# P03_SOM_CONNECTOR_CON0.net
KiCad netlist of a schematic drawn in Altium Designer
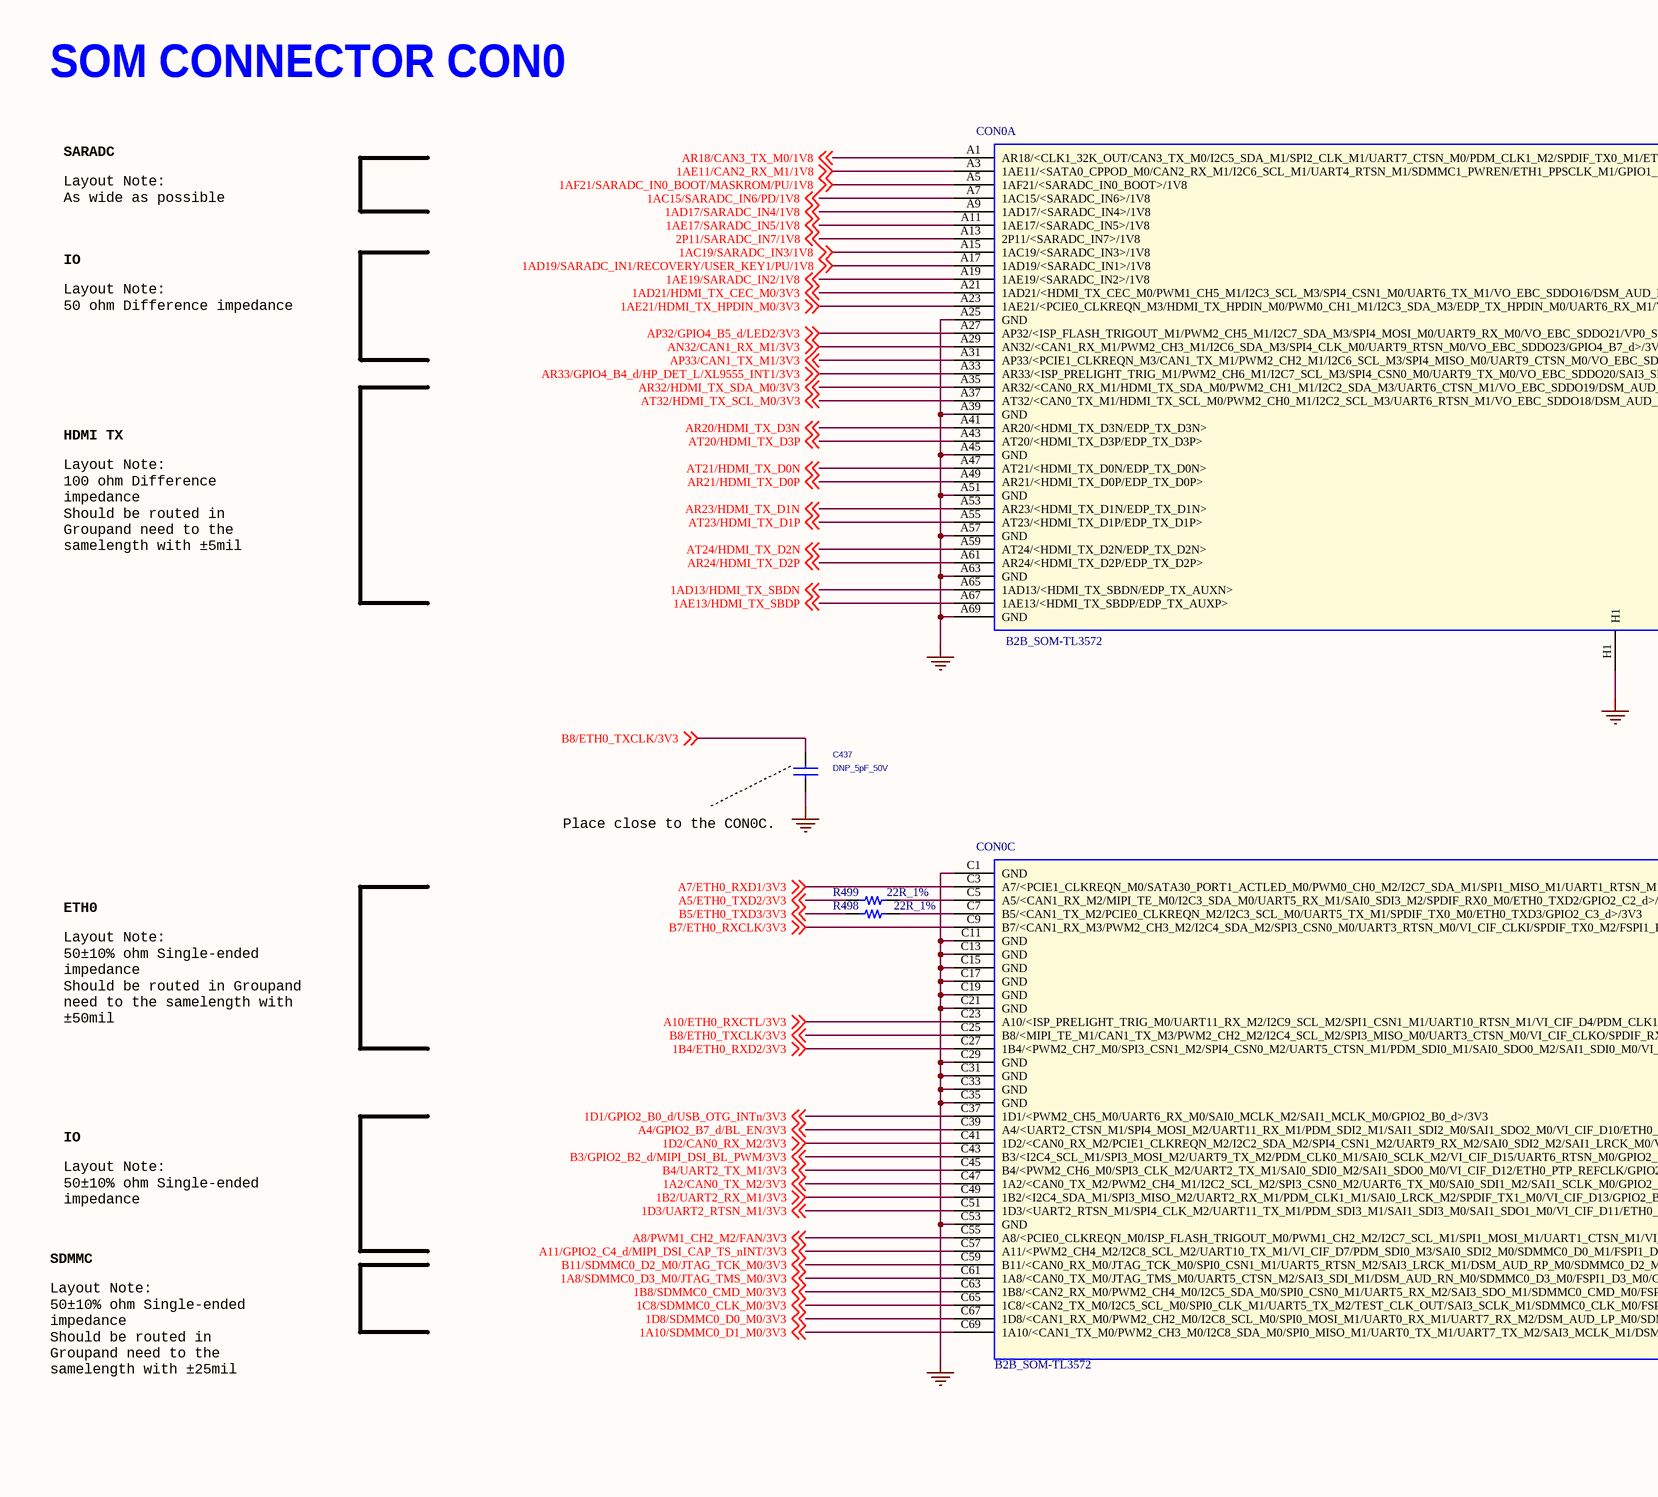
[diagram p0: P03_SOM CONNECTOR CON0.SchDoc, top left]
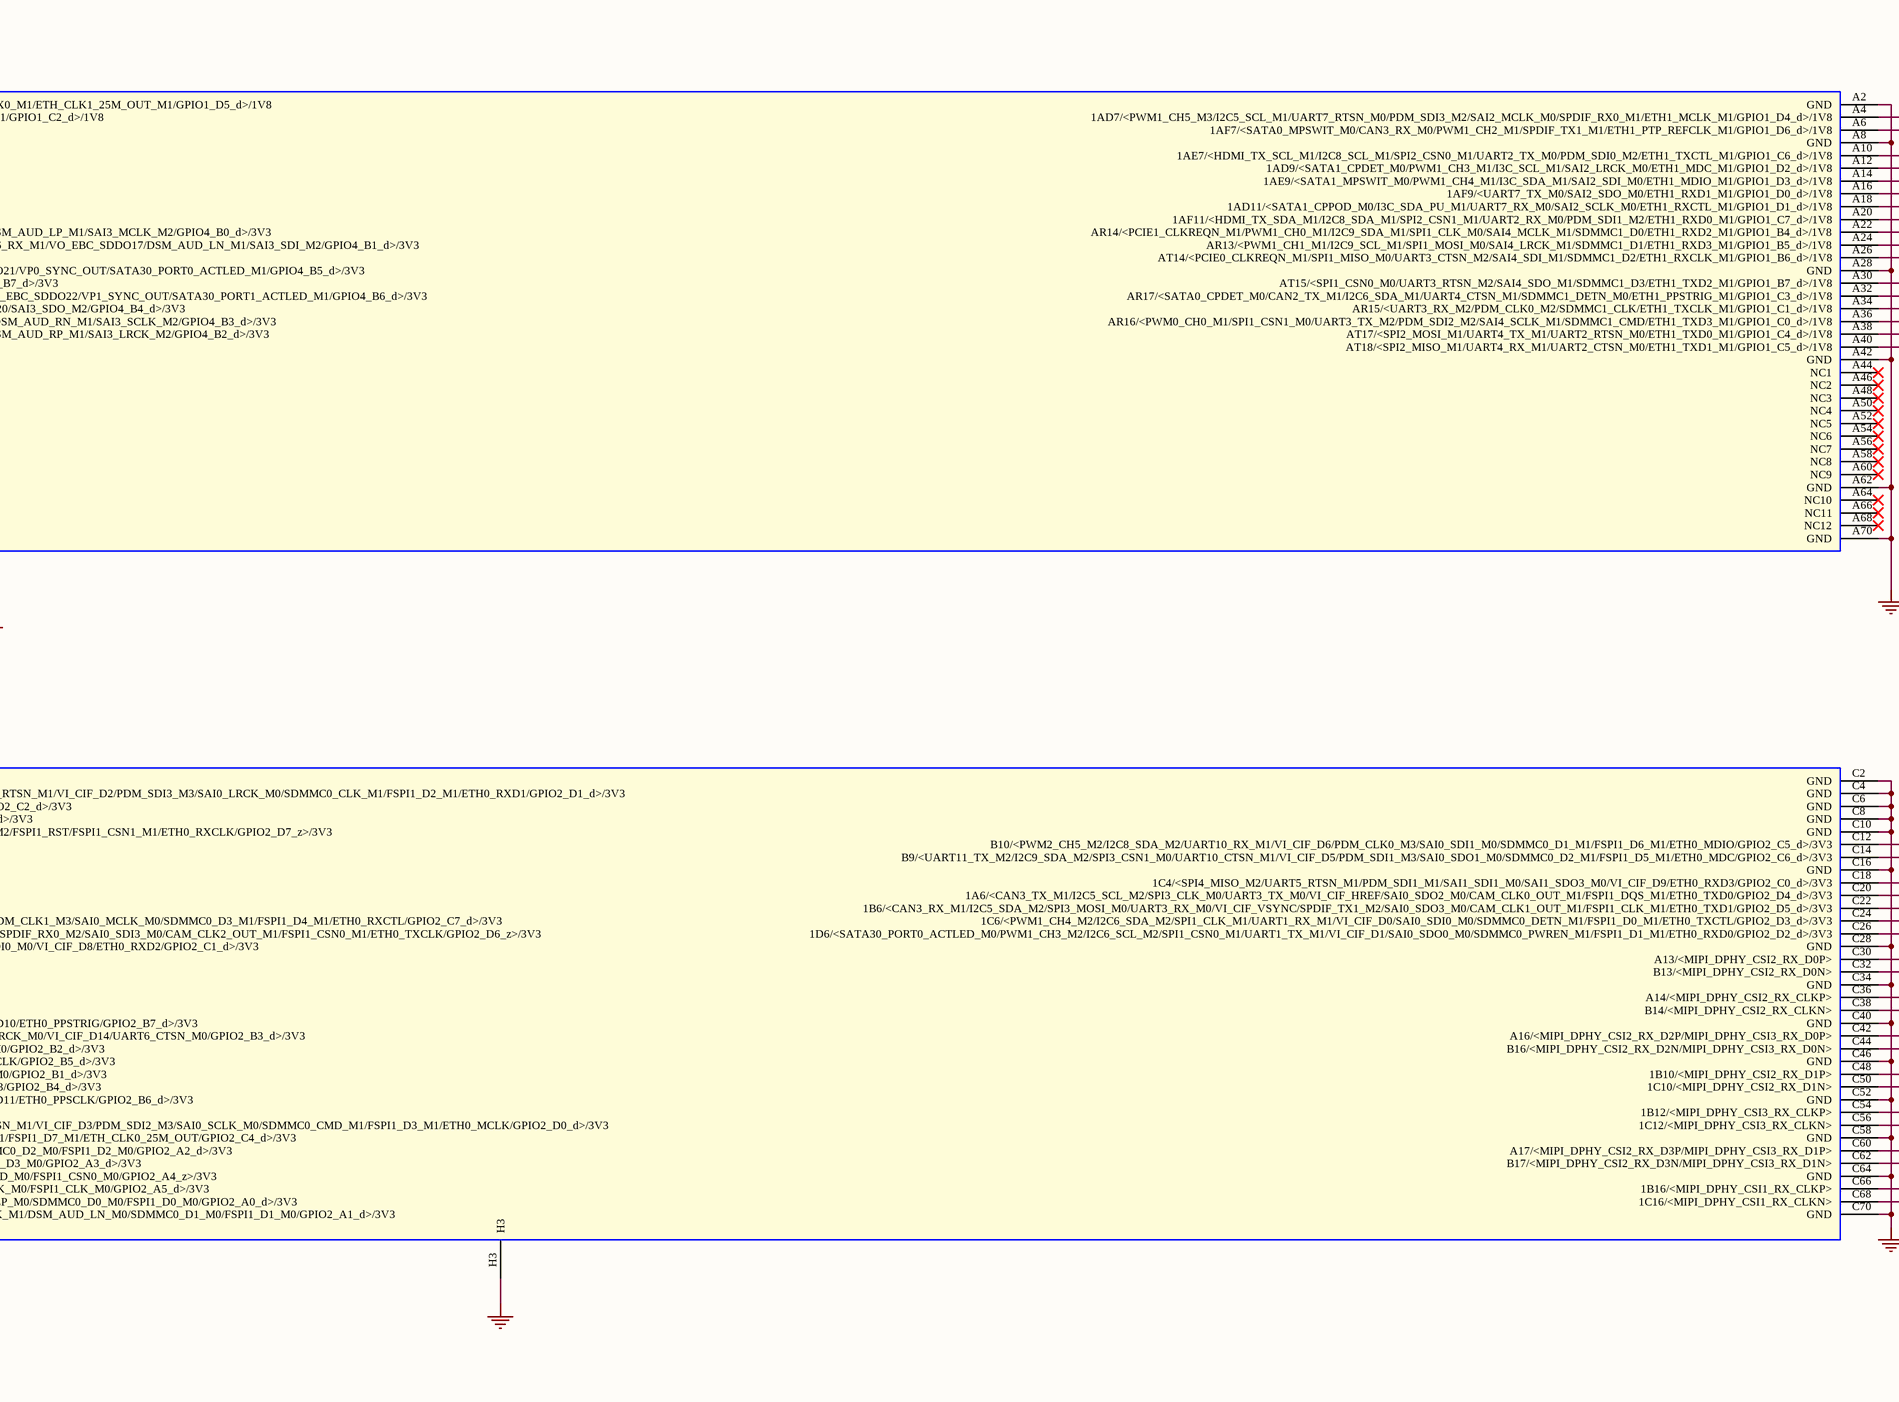
[diagram p1: P03_SOM CONNECTOR CON0.SchDoc, top middle]
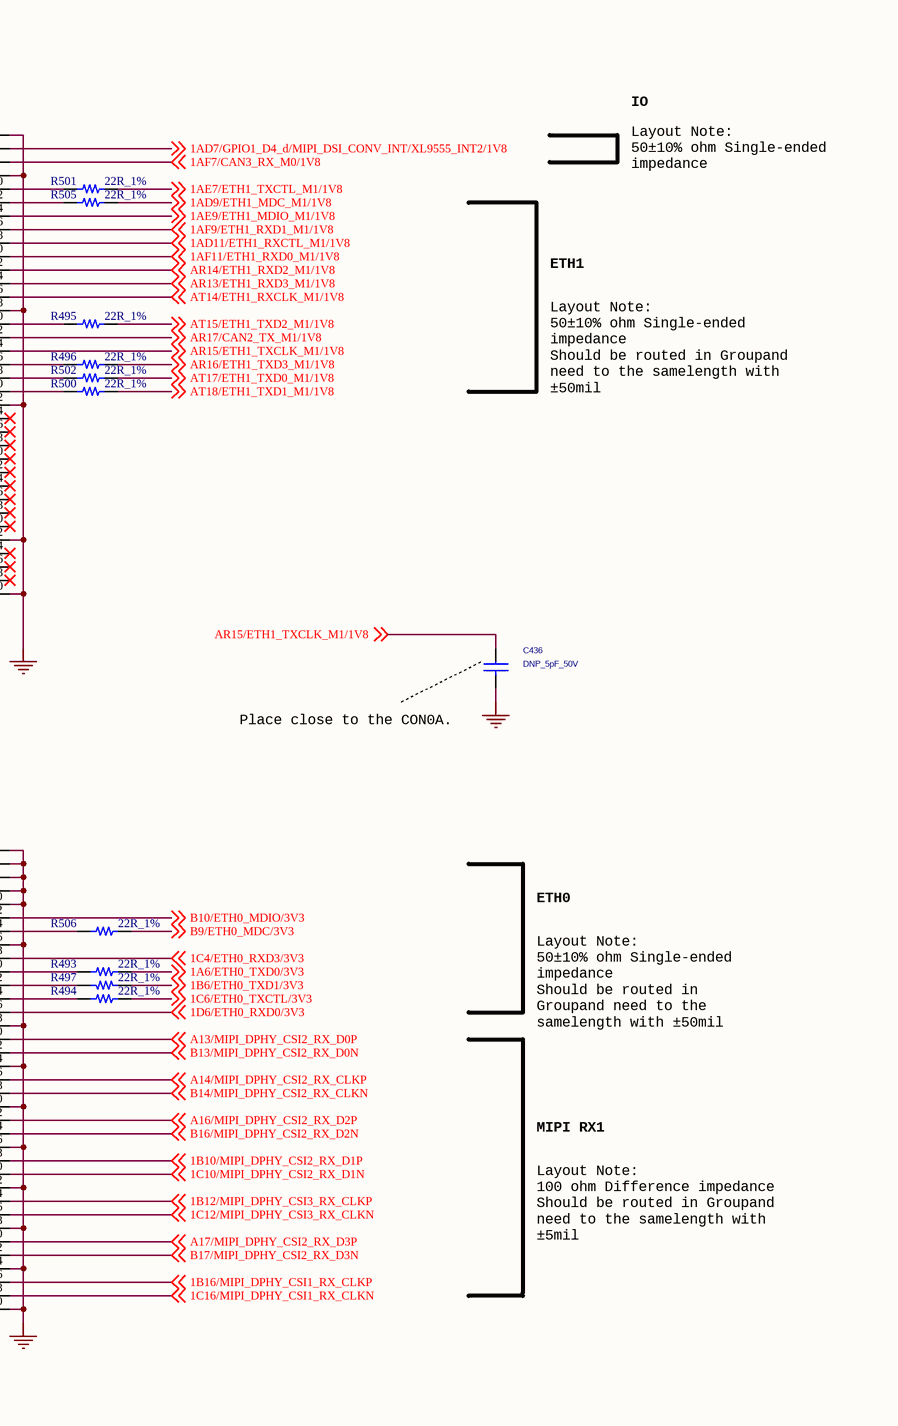
[diagram p2: P03_SOM CONNECTOR CON0.SchDoc, top right]
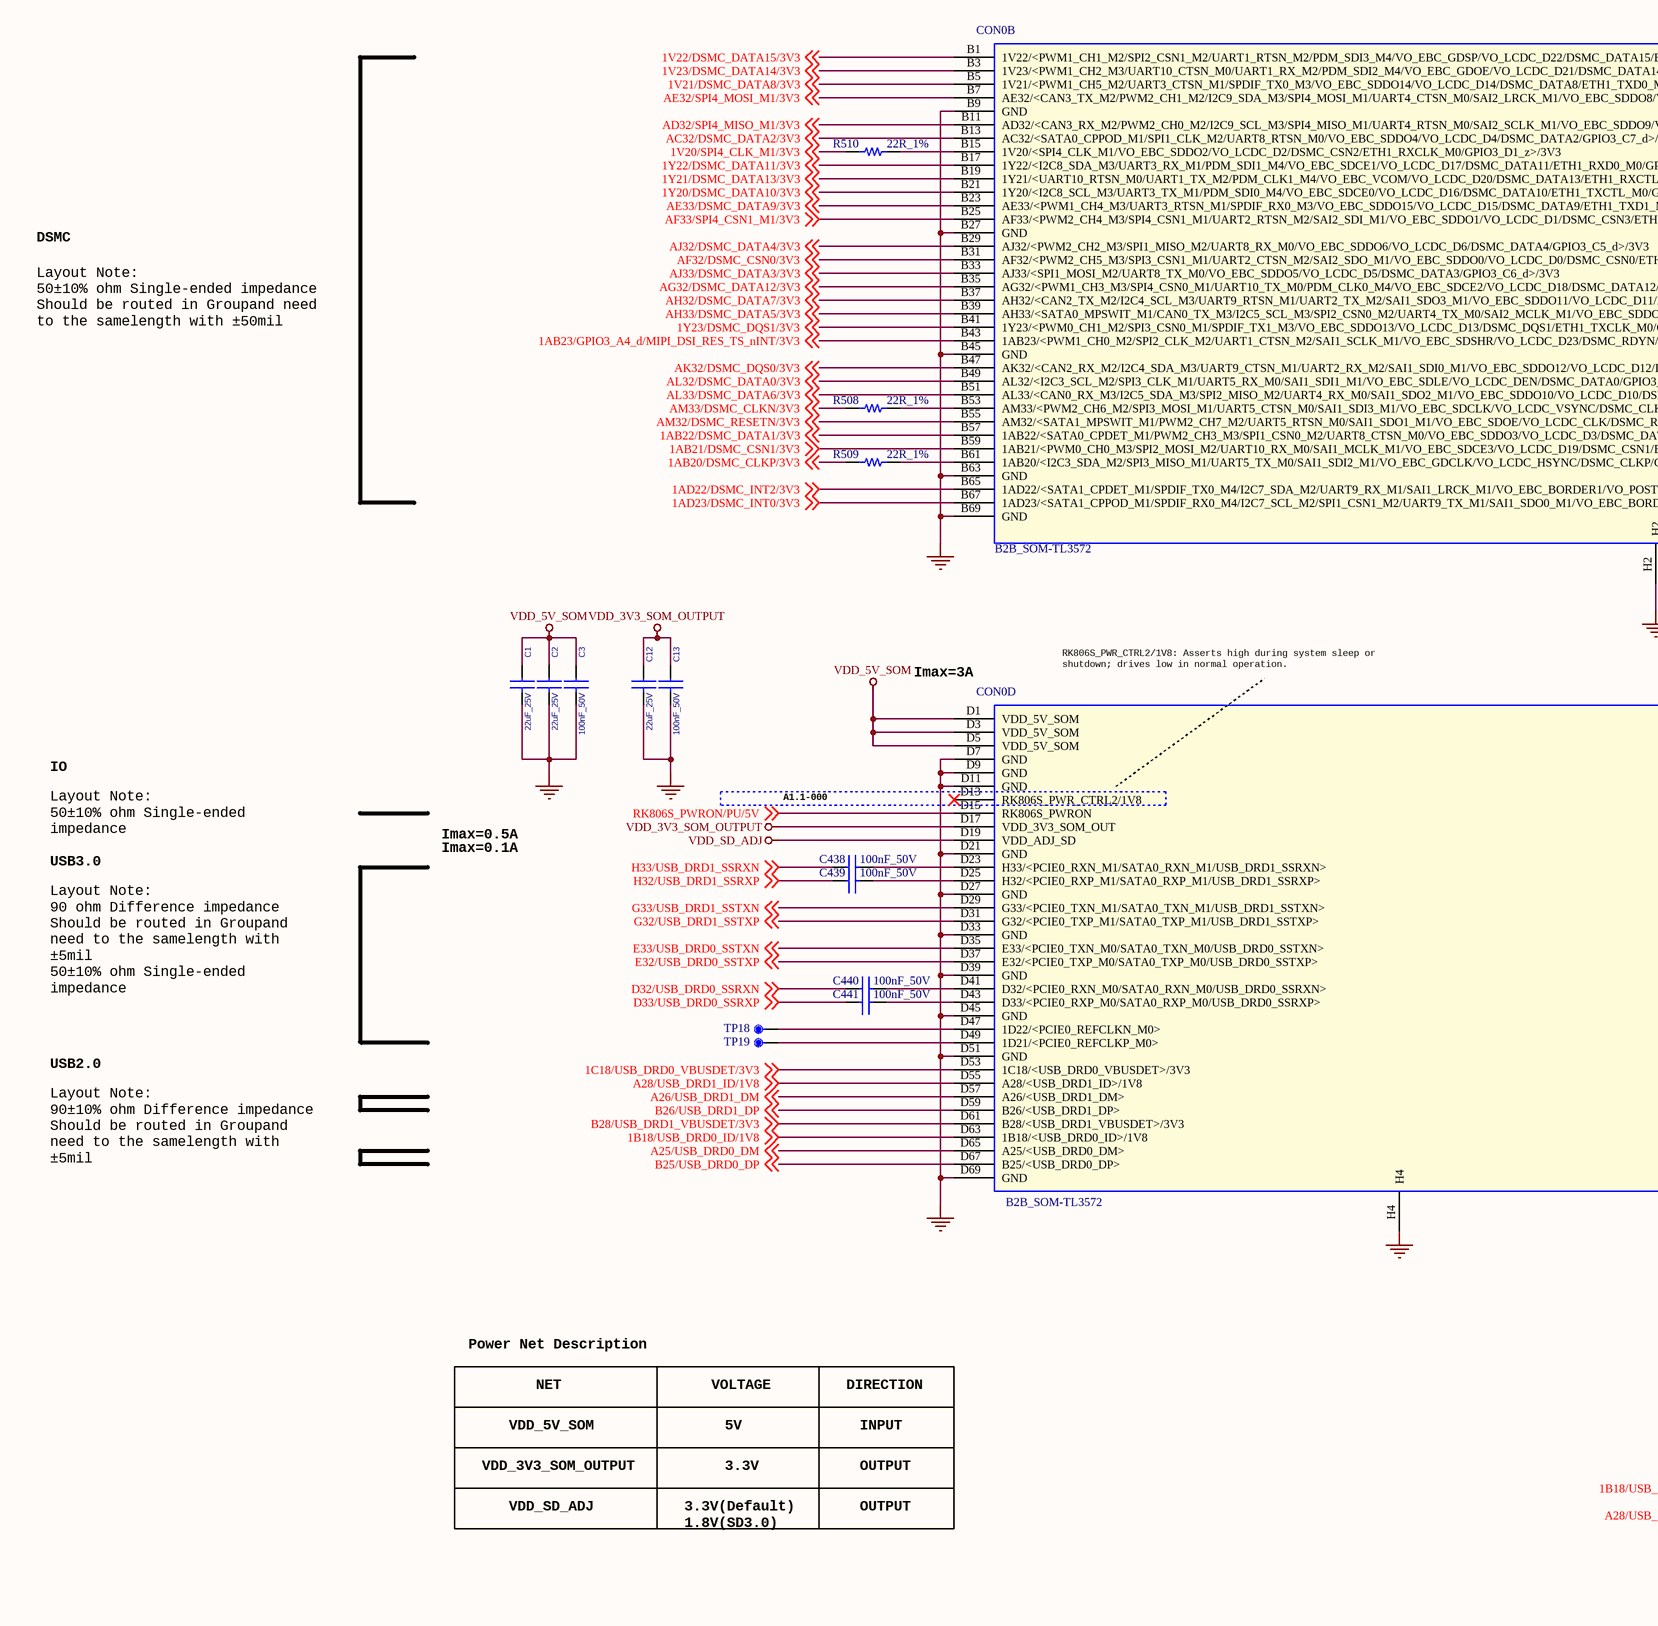
[diagram p3: P03_SOM CONNECTOR CON0.SchDoc, bottom left]
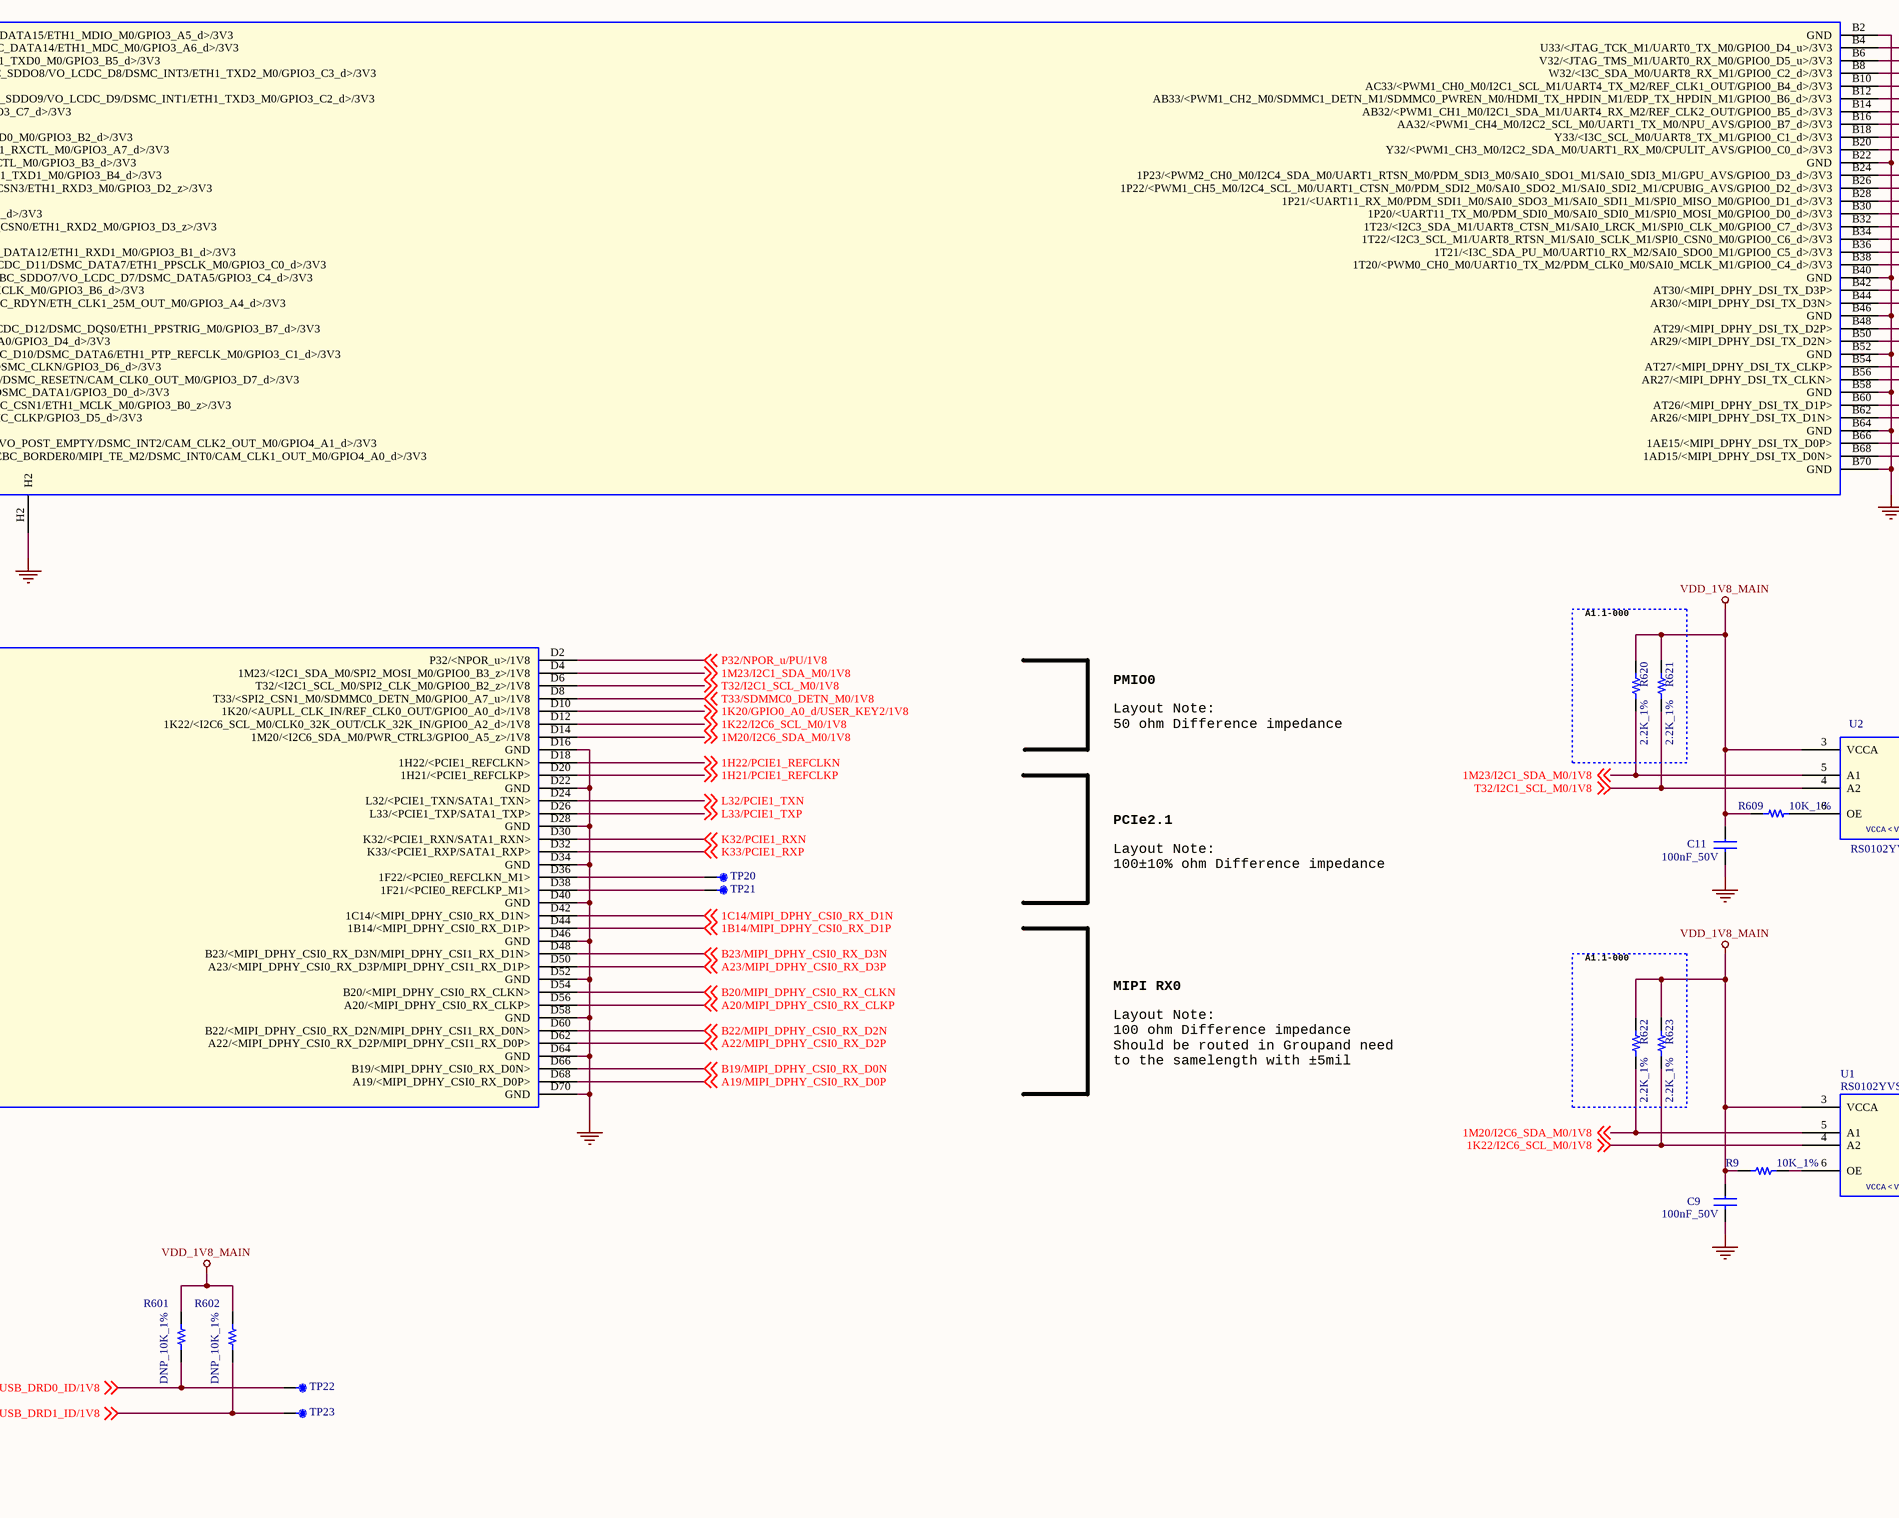
[diagram p4: P03_SOM CONNECTOR CON0.SchDoc, bottom middle]
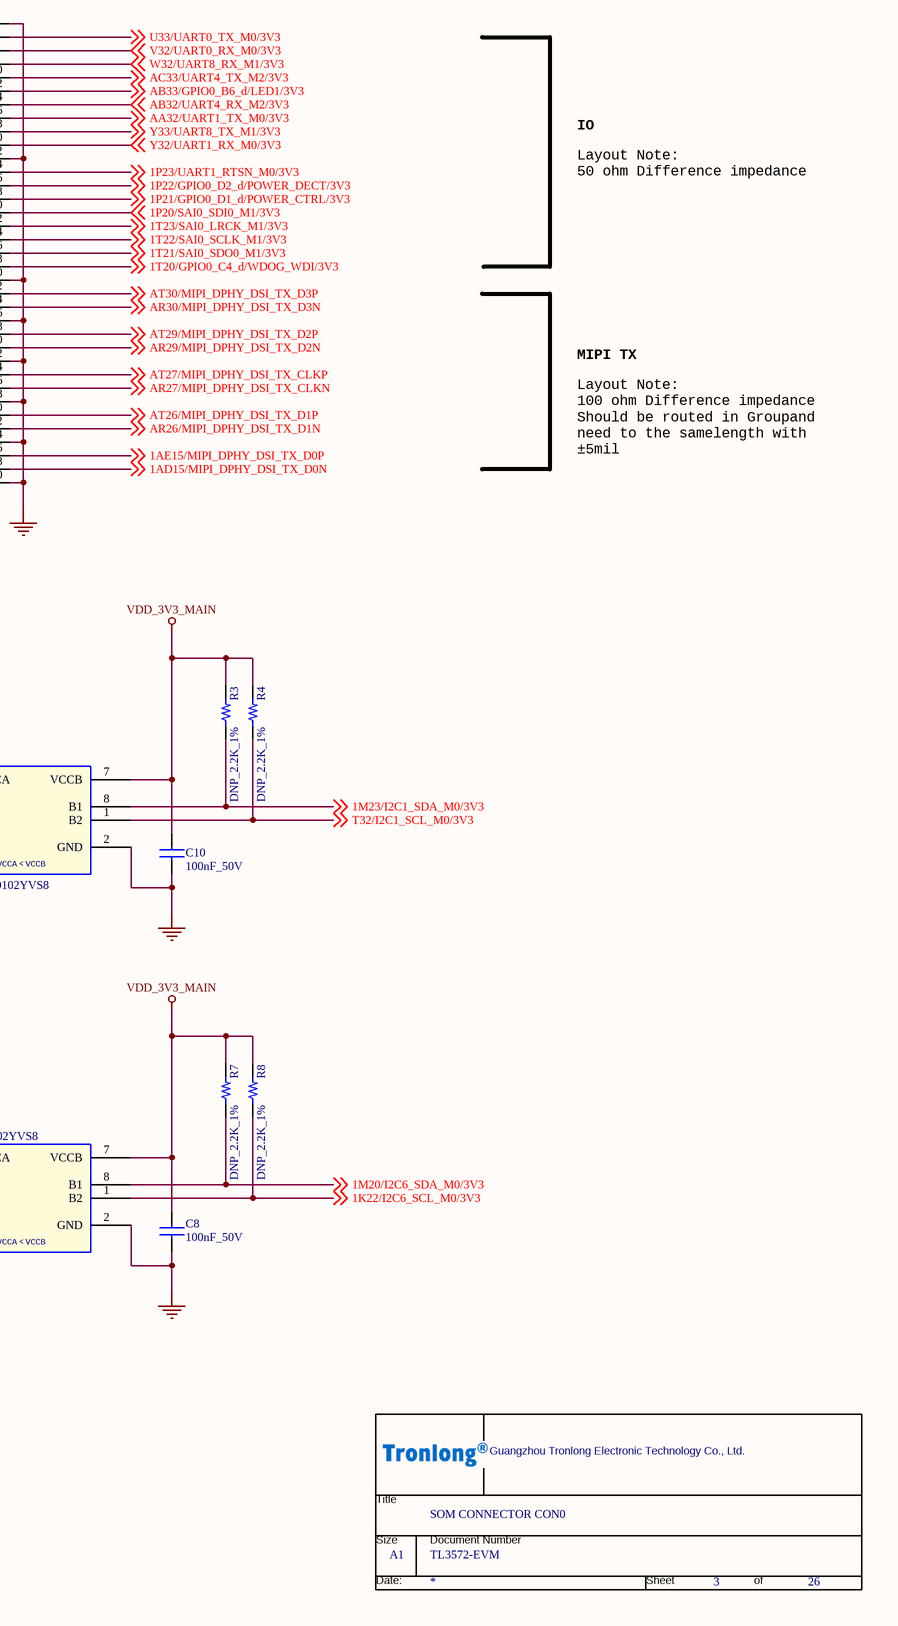
[diagram p5: P03_SOM CONNECTOR CON0.SchDoc, bottom right]

(export (version "E")
  (design (tool "Eeschema 10.0.6"))
  (components
    (comp (ref "C1")
      (value "22uF_25V")
      (footprint "C0805")
      (description "贴片陶瓷电容,22uF,20%,25V,X5R")
      (fields
        (field (name "MANUFACTURER") "广东风华高新科技股份有限公司（FH）")
        (field (name "MANUFACTURER PARTNUMBER") "0805X226M250NT")
      )
      (libsource (lib "*") (part "CAP NP_Dup2"))
    )
    (comp (ref "C2")
      (value "22uF_25V")
      (footprint "C0805")
      (description "贴片陶瓷电容,22uF,20%,25V,X5R")
      (fields
        (field (name "MANUFACTURER") "广东风华高新科技股份有限公司（FH）")
        (field (name "MANUFACTURER PARTNUMBER") "0805X226M250NT")
      )
      (libsource (lib "*") (part "CAP NP_Dup2"))
    )
    (comp (ref "C3")
      (value "100nF_50V")
      (footprint "C0402")
      (description "贴片陶瓷电容,100nF,10%,50V,X7R")
      (fields
        (field (name "MANUFACTURER PARTNUMBER") "0402B104K500NT")
        (field (name "MANUFACTURER") "广东风华高新科技股份有限公司（FH）")
      )
      (libsource (lib "*") (part "CAP NP_Dup2"))
    )
    (comp (ref "C8")
      (value "100nF_50V")
      (footprint "C0402")
      (description "贴片陶瓷电容,100nF,10%,50V,X7R")
      (fields
        (field (name "MANUFACTURER PARTNUMBER") "0402B104K500NT")
        (field (name "MANUFACTURER") "广东风华高新科技股份有限公司（FH）")
      )
      (libsource (lib "*") (part "CAP NP_Dup3"))
    )
    (comp (ref "C9")
      (value "100nF_50V")
      (footprint "C0402")
      (description "贴片陶瓷电容,100nF,10%,50V,X7R")
      (fields
        (field (name "MANUFACTURER PARTNUMBER") "0402B104K500NT")
        (field (name "MANUFACTURER") "广东风华高新科技股份有限公司（FH）")
      )
      (libsource (lib "*") (part "CAP NP_Dup3"))
    )
    (comp (ref "C10")
      (value "100nF_50V")
      (footprint "C0402")
      (description "贴片陶瓷电容,100nF,10%,50V,X7R")
      (fields
        (field (name "MANUFACTURER PARTNUMBER") "0402B104K500NT")
        (field (name "MANUFACTURER") "广东风华高新科技股份有限公司（FH）")
      )
      (libsource (lib "*") (part "CAP NP_Dup3"))
    )
    (comp (ref "C11")
      (value "100nF_50V")
      (footprint "C0402")
      (description "贴片陶瓷电容,100nF,10%,50V,X7R")
      (fields
        (field (name "MANUFACTURER") "广东风华高新科技股份有限公司（FH）")
        (field (name "MANUFACTURER PARTNUMBER") "0402B104K500NT")
      )
      (libsource (lib "*") (part "CAP NP_Dup3"))
    )
    (comp (ref "C12")
      (value "22uF_25V")
      (footprint "C0805")
      (description "贴片陶瓷电容,22uF,20%,25V,X5R")
      (fields
        (field (name "MANUFACTURER PARTNUMBER") "0805X226M250NT")
        (field (name "MANUFACTURER") "广东风华高新科技股份有限公司（FH）")
      )
      (libsource (lib "*") (part "CAP NP_Dup2"))
    )
    (comp (ref "C13")
      (value "100nF_50V")
      (footprint "C0402")
      (description "贴片陶瓷电容,100nF,10%,50V,X7R")
      (fields
        (field (name "MANUFACTURER PARTNUMBER") "0402B104K500NT")
        (field (name "MANUFACTURER") "广东风华高新科技股份有限公司（FH）")
      )
      (libsource (lib "*") (part "CAP NP_Dup2"))
    )
    (comp (ref "C436")
      (value "DNP_5pF_50V")
      (footprint "C0402")
      (description "贴片陶瓷电容,22pF,5%,50V,COG")
      (fields
        (field (name "MANUFACTURER") "广东风华高新科技股份有限公司（FH）")
        (field (name "MANUFACTURER PARTNUMBER") "0402CG220J500NT")
      )
      (libsource (lib "*") (part "CAP NP_Dup2"))
    )
    (comp (ref "C437")
      (value "DNP_5pF_50V")
      (footprint "C0402")
      (description "贴片陶瓷电容,22pF,5%,50V,COG")
      (fields
        (field (name "MANUFACTURER") "广东风华高新科技股份有限公司（FH）")
        (field (name "MANUFACTURER PARTNUMBER") "0402CG220J500NT")
      )
      (libsource (lib "*") (part "CAP NP_Dup2"))
    )
    (comp (ref "C438")
      (value "100nF_50V")
      (footprint "C0402")
      (description "贴片陶瓷电容,100nF,10%,50V,X7R")
      (fields
        (field (name "MANUFACTURER PARTNUMBER") "0402B104K500NT")
        (field (name "MANUFACTURER") "广东风华高新科技股份有限公司（FH）")
      )
      (libsource (lib "*") (part "CAP NP_Dup2"))
    )
    (comp (ref "C439")
      (value "100nF_50V")
      (footprint "C0402")
      (description "贴片陶瓷电容,100nF,10%,50V,X7R")
      (fields
        (field (name "MANUFACTURER") "广东风华高新科技股份有限公司（FH）")
        (field (name "MANUFACTURER PARTNUMBER") "0402B104K500NT")
      )
      (libsource (lib "*") (part "CAP NP_Dup2"))
    )
    (comp (ref "C440")
      (value "100nF_50V")
      (footprint "C0402")
      (description "贴片陶瓷电容,100nF,10%,50V,X7R")
      (fields
        (field (name "MANUFACTURER PARTNUMBER") "0402B104K500NT")
        (field (name "MANUFACTURER") "广东风华高新科技股份有限公司（FH）")
      )
      (libsource (lib "*") (part "CAP NP_Dup2"))
    )
    (comp (ref "C441")
      (value "100nF_50V")
      (footprint "C0402")
      (description "贴片陶瓷电容,100nF,10%,50V,X7R")
      (fields
        (field (name "MANUFACTURER PARTNUMBER") "0402B104K500NT")
        (field (name "MANUFACTURER") "广东风华高新科技股份有限公司（FH）")
      )
      (libsource (lib "*") (part "CAP NP_Dup2"))
    )
    (comp (ref "CON0")
      (value "B2B_SOM-TL3572")
      (footprint "B2B_SOM-TL3572")
      (libsource (lib "TL3572-EVM-A1.1-000-r-202609030936") (part "B2B_SOM-TL3572"))
    )
    (comp (ref "R3")
      (value "DNP_2.2K_1%")
      (footprint "R0402")
      (description "贴片电阻,2.2K,±1%,1/16W")
      (fields
        (field (name "MANUFACTURER PARTNUMBER") "RC-02K2201FT")
        (field (name "MANUFACTURER") "广东风华高新科技股份有限公司（FH）")
      )
      (libsource (lib "*") (part "Resistor_Dup4"))
    )
    (comp (ref "R4")
      (value "DNP_2.2K_1%")
      (footprint "R0402")
      (description "贴片电阻,2.2K,±1%,1/16W")
      (fields
        (field (name "MANUFACTURER PARTNUMBER") "RC-02K2201FT")
        (field (name "MANUFACTURER") "广东风华高新科技股份有限公司（FH）")
      )
      (libsource (lib "*") (part "Resistor_Dup4"))
    )
    (comp (ref "R7")
      (value "DNP_2.2K_1%")
      (footprint "R0402")
      (description "贴片电阻,2.2K,±1%,1/16W")
      (fields
        (field (name "MANUFACTURER") "广东风华高新科技股份有限公司（FH）")
        (field (name "MANUFACTURER PARTNUMBER") "RC-02K2201FT")
      )
      (libsource (lib "*") (part "Resistor_Dup4"))
    )
    (comp (ref "R8")
      (value "DNP_2.2K_1%")
      (footprint "R0402")
      (description "贴片电阻,2.2K,±1%,1/16W")
      (fields
        (field (name "MANUFACTURER PARTNUMBER") "RC-02K2201FT")
        (field (name "MANUFACTURER") "广东风华高新科技股份有限公司（FH）")
      )
      (libsource (lib "*") (part "Resistor_Dup4"))
    )
    (comp (ref "R9")
      (value "10K_1%")
      (footprint "R0402")
      (description "贴片电阻,10K,±1%,1/16W")
      (fields
        (field (name "MANUFACTURER") "广东风华高新科技股份有限公司（FH）")
        (field (name "MANUFACTURER PARTNUMBER") "RC-02K1002FT")
      )
      (libsource (lib "*") (part "Resistor_Dup4"))
    )
    (comp (ref "R493")
      (value "22R_1%")
      (footprint "R0402")
      (description "贴片电阻,22R,±1%,1/16W")
      (fields
        (field (name "MANUFACTURER") "广东风华高新科技股份有限公司（FH）")
        (field (name "MANUFACTURER PARTNUMBER") "RC-02K22R0FT")
      )
      (libsource (lib "*") (part "Resistor_Dup3"))
    )
    (comp (ref "R494")
      (value "22R_1%")
      (footprint "R0402")
      (description "贴片电阻,22R,±1%,1/16W")
      (fields
        (field (name "MANUFACTURER PARTNUMBER") "RC-02K22R0FT")
        (field (name "MANUFACTURER") "广东风华高新科技股份有限公司（FH）")
      )
      (libsource (lib "*") (part "Resistor_Dup3"))
    )
    (comp (ref "R495")
      (value "22R_1%")
      (footprint "R0402")
      (description "贴片电阻,22R,±1%,1/16W")
      (fields
        (field (name "MANUFACTURER PARTNUMBER") "RC-02K22R0FT")
        (field (name "MANUFACTURER") "广东风华高新科技股份有限公司（FH）")
      )
      (libsource (lib "*") (part "Resistor_Dup3"))
    )
    (comp (ref "R496")
      (value "22R_1%")
      (footprint "R0402")
      (description "贴片电阻,22R,±1%,1/16W")
      (fields
        (field (name "MANUFACTURER PARTNUMBER") "RC-02K22R0FT")
        (field (name "MANUFACTURER") "广东风华高新科技股份有限公司（FH）")
      )
      (libsource (lib "*") (part "Resistor_Dup3"))
    )
    (comp (ref "R497")
      (value "22R_1%")
      (footprint "R0402")
      (description "贴片电阻,22R,±1%,1/16W")
      (fields
        (field (name "MANUFACTURER PARTNUMBER") "RC-02K22R0FT")
        (field (name "MANUFACTURER") "广东风华高新科技股份有限公司（FH）")
      )
      (libsource (lib "*") (part "Resistor_Dup3"))
    )
    (comp (ref "R498")
      (value "22R_1%")
      (footprint "R0402")
      (description "贴片电阻,22R,±1%,1/16W")
      (fields
        (field (name "MANUFACTURER PARTNUMBER") "RC-02K22R0FT")
        (field (name "MANUFACTURER") "广东风华高新科技股份有限公司（FH）")
      )
      (libsource (lib "*") (part "Resistor_Dup3"))
    )
    (comp (ref "R499")
      (value "22R_1%")
      (footprint "R0402")
      (description "贴片电阻,22R,±1%,1/16W")
      (fields
        (field (name "MANUFACTURER") "广东风华高新科技股份有限公司（FH）")
        (field (name "MANUFACTURER PARTNUMBER") "RC-02K22R0FT")
      )
      (libsource (lib "*") (part "Resistor_Dup3"))
    )
    (comp (ref "R500")
      (value "22R_1%")
      (footprint "R0402")
      (description "贴片电阻,22R,±1%,1/16W")
      (fields
        (field (name "MANUFACTURER") "广东风华高新科技股份有限公司（FH）")
        (field (name "MANUFACTURER PARTNUMBER") "RC-02K22R0FT")
      )
      (libsource (lib "*") (part "Resistor_Dup3"))
    )
    (comp (ref "R501")
      (value "22R_1%")
      (footprint "R0402")
      (description "贴片电阻,22R,±1%,1/16W")
      (fields
        (field (name "MANUFACTURER") "广东风华高新科技股份有限公司（FH）")
        (field (name "MANUFACTURER PARTNUMBER") "RC-02K22R0FT")
      )
      (libsource (lib "*") (part "Resistor_Dup3"))
    )
    (comp (ref "R502")
      (value "22R_1%")
      (footprint "R0402")
      (description "贴片电阻,22R,±1%,1/16W")
      (fields
        (field (name "MANUFACTURER PARTNUMBER") "RC-02K22R0FT")
        (field (name "MANUFACTURER") "广东风华高新科技股份有限公司（FH）")
      )
      (libsource (lib "*") (part "Resistor_Dup3"))
    )
    (comp (ref "R505")
      (value "22R_1%")
      (footprint "R0402")
      (description "贴片电阻,22R,±1%,1/16W")
      (fields
        (field (name "MANUFACTURER") "广东风华高新科技股份有限公司（FH）")
        (field (name "MANUFACTURER PARTNUMBER") "RC-02K22R0FT")
      )
      (libsource (lib "*") (part "Resistor_Dup3"))
    )
    (comp (ref "R506")
      (value "22R_1%")
      (footprint "R0402")
      (description "贴片电阻,22R,±1%,1/16W")
      (fields
        (field (name "MANUFACTURER PARTNUMBER") "RC-02K22R0FT")
        (field (name "MANUFACTURER") "广东风华高新科技股份有限公司（FH）")
      )
      (libsource (lib "*") (part "Resistor_Dup3"))
    )
    (comp (ref "R508")
      (value "22R_1%")
      (footprint "R0402")
      (description "贴片电阻,22R,±1%,1/16W")
      (fields
        (field (name "MANUFACTURER") "广东风华高新科技股份有限公司（FH）")
        (field (name "MANUFACTURER PARTNUMBER") "RC-02K22R0FT")
      )
      (libsource (lib "*") (part "Resistor_Dup3"))
    )
    (comp (ref "R509")
      (value "22R_1%")
      (footprint "R0402")
      (description "贴片电阻,22R,±1%,1/16W")
      (fields
        (field (name "MANUFACTURER") "广东风华高新科技股份有限公司（FH）")
        (field (name "MANUFACTURER PARTNUMBER") "RC-02K22R0FT")
      )
      (libsource (lib "*") (part "Resistor_Dup3"))
    )
    (comp (ref "R510")
      (value "22R_1%")
      (footprint "R0402")
      (description "贴片电阻,22R,±1%,1/16W")
      (fields
        (field (name "MANUFACTURER") "广东风华高新科技股份有限公司（FH）")
        (field (name "MANUFACTURER PARTNUMBER") "RC-02K22R0FT")
      )
      (libsource (lib "*") (part "Resistor_Dup3"))
    )
    (comp (ref "R601")
      (value "DNP_10K_1%")
      (footprint "R0402")
      (description "贴片电阻,10K,±1%,1/16W")
      (fields
        (field (name "MANUFACTURER PARTNUMBER") "RC-02K1002FT")
        (field (name "MANUFACTURER") "广东风华高新科技股份有限公司（FH）")
      )
      (libsource (lib "*") (part "Resistor_Dup4"))
    )
    (comp (ref "R602")
      (value "DNP_10K_1%")
      (footprint "R0402")
      (description "贴片电阻,10K,±1%,1/16W")
      (fields
        (field (name "MANUFACTURER") "广东风华高新科技股份有限公司（FH）")
        (field (name "MANUFACTURER PARTNUMBER") "RC-02K1002FT")
      )
      (libsource (lib "*") (part "Resistor_Dup4"))
    )
    (comp (ref "R609")
      (value "10K_1%")
      (footprint "R0402")
      (description "贴片电阻,10K,±1%,1/16W")
      (fields
        (field (name "MANUFACTURER") "广东风华高新科技股份有限公司（FH）")
        (field (name "MANUFACTURER PARTNUMBER") "RC-02K1002FT")
      )
      (libsource (lib "*") (part "Resistor_Dup4"))
    )
    (comp (ref "R620")
      (value "2.2K_1%")
      (footprint "R0402")
      (description "贴片电阻,2.2K,±1%,1/16W")
      (fields
        (field (name "MANUFACTURER") "广东风华高新科技股份有限公司（FH）")
        (field (name "MANUFACTURER PARTNUMBER") "RC-02K2201FT")
      )
      (libsource (lib "*") (part "Resistor_Dup4"))
    )
    (comp (ref "R621")
      (value "2.2K_1%")
      (footprint "R0402")
      (description "贴片电阻,2.2K,±1%,1/16W")
      (fields
        (field (name "MANUFACTURER") "广东风华高新科技股份有限公司（FH）")
        (field (name "MANUFACTURER PARTNUMBER") "RC-02K2201FT")
      )
      (libsource (lib "*") (part "Resistor_Dup4"))
    )
    (comp (ref "R622")
      (value "2.2K_1%")
      (footprint "R0402")
      (description "贴片电阻,2.2K,±1%,1/16W")
      (fields
        (field (name "MANUFACTURER PARTNUMBER") "RC-02K2201FT")
        (field (name "MANUFACTURER") "广东风华高新科技股份有限公司（FH）")
      )
      (libsource (lib "*") (part "Resistor_Dup4"))
    )
    (comp (ref "R623")
      (value "2.2K_1%")
      (footprint "R0402")
      (description "贴片电阻,2.2K,±1%,1/16W")
      (fields
        (field (name "MANUFACTURER PARTNUMBER") "RC-02K2201FT")
        (field (name "MANUFACTURER") "广东风华高新科技股份有限公司（FH）")
      )
      (libsource (lib "*") (part "Resistor_Dup4"))
    )
    (comp (ref "TP18")
      (value "SMT TP")
      (footprint "TP30")
      (description "/")
      (libsource (lib "*") (part "TP-S40"))
    )
    (comp (ref "TP19")
      (value "SMT TP")
      (footprint "TP30")
      (description "/")
      (libsource (lib "*") (part "TP-S40"))
    )
    (comp (ref "TP20")
      (value "SMT TP")
      (footprint "TP30")
      (description "/")
      (libsource (lib "*") (part "TP-S40"))
    )
    (comp (ref "TP21")
      (value "SMT TP")
      (footprint "TP30")
      (description "/")
      (libsource (lib "*") (part "TP-S40"))
    )
    (comp (ref "TP22")
      (value "SMT TP")
      (footprint "TP30")
      (description "/")
      (libsource (lib "*") (part "TP-S40"))
    )
    (comp (ref "TP23")
      (value "SMT TP")
      (footprint "TP30")
      (description "/")
      (libsource (lib "*") (part "TP-S40"))
    )
    (comp (ref "U1")
      (value "RS0102YVS8")
      (footprint "SOP8-20-91")
      (description "2位双向电平转换器")
      (fields (field (name "MANUFACTURER") "江苏润石科技有限公司（RUNIC）"))
      (libsource (lib "*") (part "TXS0102DCUR_0"))
    )
    (comp (ref "U2")
      (value "RS0102YVS8")
      (footprint "SOP8-20-91")
      (description "2位双向电平转换器")
      (fields (field (name "MANUFACTURER") "江苏润石科技有限公司（RUNIC）"))
      (libsource (lib "*") (part "TXS0102DCUR_0"))
    )
  )
  (nets
    (net (code "1") (name "1A2{slash}CAN0_TX_M2{slash}3V3") (class "Default")
      (node (ref "CON0") (pin "C47") (pinfunction "1A2/<CAN0_TX_M2/PWM2_CH4_M1/I2C2_SCL_M2/SPI3_CSN0_M2/UART6_TX_M0/SAI0_SDI1_M2/SAI1_SCLK_M0/GPIO2_B1_d>/3V3_C47") (pintype "passive"))
    )
    (net (code "2") (name "1A6{slash}ETH0_TXD0{slash}3V3") (class "Default")
      (node (ref "R493") (pin "2") (pinfunction "2_2") (pintype "passive"))
    )
    (net (code "3") (name "1A8{slash}SDMMC0_D3_M0{slash}JTAG_TMS_M0{slash}3V3") (class "Default")
      (node (ref "CON0") (pin "C61") (pinfunction "1A8/<CAN0_TX_M0/JTAG_TMS_M0/UART5_CTSN_M2/SAI3_SDI_M1/DSM_AUD_RN_M0/SDMMC0_D3_M0/FSPI1_D3_M0/GPIO2_A3_d>/3V3_C61") (pintype "passive"))
    )
    (net (code "4") (name "1A10{slash}SDMMC0_D1_M0{slash}3V3") (class "Default")
      (node (ref "CON0") (pin "C69") (pinfunction "1A10/<CAN1_TX_M0/PWM2_CH3_M0/I2C8_SDA_M0/SPI0_MISO_M1/UART0_TX_M1/UART7_TX_M2/SAI3_MCLK_M1/DSM_AUD_LN_M0/SDMMC0_D1_M0/FSPI1_D1_M0/GPIO2_A1_d>/3V3_C69") (pintype "passive"))
    )
    (net (code "5") (name "1AB20{slash}DSMC_CLKP{slash}3V3") (class "Default")
      (node (ref "R509") (pin "1") (pinfunction "1_1") (pintype "passive"))
    )
    (net (code "6") (name "1AB21{slash}DSMC_CSN1{slash}3V3") (class "Default")
      (node (ref "CON0") (pin "B59") (pinfunction "1AB21/<PWM0_CH0_M3/SPI2_MOSI_M2/UART10_RX_M0/SAI1_MCLK_M1/VO_EBC_SDCE3/VO_LCDC_D19/DSMC_CSN1/ETH1_MCLK_M0/GPIO3_B0_z>/3V3_B59") (pintype "passive"))
    )
    (net (code "7") (name "1AB22{slash}DSMC_DATA1{slash}3V3") (class "Default")
      (node (ref "CON0") (pin "B57") (pinfunction "1AB22/<SATA0_CPDET_M1/PWM2_CH3_M3/SPI1_CSN0_M2/UART8_CTSN_M0/VO_EBC_SDDO3/VO_LCDC_D3/DSMC_DATA1/GPIO3_D0_d>/3V3_B57") (pintype "passive"))
    )
    (net (code "8") (name "1AB23{slash}GPIO3_A4_d{slash}MIPI_DSI_RES_TS_nINT{slash}3V3") (class "Default")
      (node (ref "CON0") (pin "B43") (pinfunction "1AB23/<PWM1_CH0_M2/SPI2_CLK_M2/UART1_CTSN_M2/SAI1_SCLK_M1/VO_EBC_SDSHR/VO_LCDC_D23/DSMC_RDYN/ETH_CLK1_25M_OUT_M0/GPIO3_A4_d>/3V3_B43") (pintype "passive"))
    )
    (net (code "9") (name "1AC15{slash}SARADC_IN6{slash}PD{slash}1V8") (class "Default")
      (node (ref "CON0") (pin "A7") (pinfunction "1AC15/<SARADC_IN6>/1V8_A7") (pintype "power_in"))
    )
    (net (code "10") (name "1AC19{slash}SARADC_IN3{slash}1V8") (class "Default")
      (node (ref "CON0") (pin "A15") (pinfunction "1AC19/<SARADC_IN3>/1V8_A15") (pintype "passive"))
    )
    (net (code "11") (name "1AD7{slash}GPIO1_D4_d{slash}MIPI_DSI_CONV_INT{slash}XL9555_INT2{slash}1V8") (class "Default")
      (node (ref "CON0") (pin "A4") (pinfunction "1AD7/<PWM1_CH5_M3/I2C5_SCL_M1/UART7_RTSN_M0/PDM_SDI3_M2/SAI2_MCLK_M0/SPDIF_RX0_M1/ETH1_MCLK_M1/GPIO1_D4_d>/1V8_A4") (pintype "passive"))
    )
    (net (code "12") (name "1AD9{slash}ETH1_MDC_M1{slash}1V8") (class "Default")
      (node (ref "R505") (pin "2") (pinfunction "2_2") (pintype "passive"))
    )
    (net (code "13") (name "1AD11{slash}ETH1_RXCTL_M1{slash}1V8") (class "Default")
      (node (ref "CON0") (pin "A18") (pinfunction "1AD11/<SATA1_CPPOD_M0/I3C_SDA_PU_M1/UART7_RX_M0/SAI2_SCLK_M0/ETH1_RXCTL_M1/GPIO1_D1_d>/1V8_A18") (pintype "passive"))
    )
    (net (code "14") (name "1AD13{slash}HDMI_TX_SBDN") (class "Default")
      (node (ref "CON0") (pin "A65") (pinfunction "1AD13/<HDMI_TX_SBDN/EDP_TX_AUXN>_A65") (pintype "passive"))
    )
    (net (code "15") (name "1AD15{slash}MIPI_DPHY_DSI_TX_D0N") (class "Default")
      (node (ref "CON0") (pin "B68") (pinfunction "1AD15/<MIPI_DPHY_DSI_TX_D0N>_B68") (pintype "power_in"))
    )
    (net (code "16") (name "1AD17{slash}SARADC_IN4{slash}1V8") (class "Default")
      (node (ref "CON0") (pin "A9") (pinfunction "1AD17/<SARADC_IN4>/1V8_A9") (pintype "power_in"))
    )
    (net (code "17") (name "1AD19{slash}SARADC_IN1{slash}RECOVERY{slash}USER_KEY1{slash}PU{slash}1V8") (class "Default")
      (node (ref "CON0") (pin "A17") (pinfunction "1AD19/<SARADC_IN1>/1V8_A17") (pintype "passive"))
    )
    (net (code "18") (name "1AD21{slash}HDMI_TX_CEC_M0{slash}3V3") (class "Default")
      (node (ref "CON0") (pin "A21") (pinfunction "1AD21/<HDMI_TX_CEC_M0/PWM1_CH5_M1/I2C3_SCL_M3/SPI4_CSN1_M0/UART6_TX_M1/VO_EBC_SDDO16/DSM_AUD_LP_M1/SAI3_MCLK_M2/GPIO4_B0_d>/3V3_A21") (pintype "passive"))
    )
    (net (code "19") (name "1AD22{slash}DSMC_INT2{slash}3V3") (class "Default")
      (node (ref "CON0") (pin "B65") (pinfunction "1AD22/<SATA1_CPDET_M1/SPDIF_TX0_M4/I2C7_SDA_M2/UART9_RX_M1/SAI1_LRCK_M1/VO_EBC_BORDER1/VO_POST_EMPTY/DSMC_INT2/CAM_CLK2_OUT_M0/GPIO4_A1_d>/3V3_B65") (pintype "passive"))
    )
    (net (code "20") (name "1AD23{slash}DSMC_INT0{slash}3V3") (class "Default")
      (node (ref "CON0") (pin "B67") (pinfunction "1AD23/<SATA1_CPPOD_M1/SPDIF_RX0_M4/I2C7_SCL_M2/SPI1_CSN1_M2/UART9_TX_M1/SAI1_SDO0_M1/VO_EBC_BORDER0/MIPI_TE_M2/DSMC_INT0/CAM_CLK1_OUT_M0/GPIO4_A0_d>/3V3_B67") (pintype "passive"))
    )
    (net (code "21") (name "1AE7{slash}ETH1_TXCTL_M1{slash}1V8") (class "Default")
      (node (ref "R501") (pin "2") (pinfunction "2_2") (pintype "passive"))
    )
    (net (code "22") (name "1AE9{slash}ETH1_MDIO_M1{slash}1V8") (class "Default")
      (node (ref "CON0") (pin "A14") (pinfunction "1AE9/<SATA1_MPSWIT_M0/PWM1_CH4_M1/I3C_SDA_M1/SAI2_SDI_M0/ETH1_MDIO_M1/GPIO1_D3_d>/1V8_A14") (pintype "power_in"))
    )
    (net (code "23") (name "1AE11{slash}CAN2_RX_M1{slash}1V8") (class "Default")
      (node (ref "CON0") (pin "A3") (pinfunction "1AE11/<SATA0_CPPOD_M0/CAN2_RX_M1/I2C6_SCL_M1/UART4_RTSN_M1/SDMMC1_PWREN/ETH1_PPSCLK_M1/GPIO1_C2_d>/1V8_A3") (pintype "power_in"))
    )
    (net (code "24") (name "1AE13{slash}HDMI_TX_SBDP") (class "Default")
      (node (ref "CON0") (pin "A67") (pinfunction "1AE13/<HDMI_TX_SBDP/EDP_TX_AUXP>_A67") (pintype "passive"))
    )
    (net (code "25") (name "1AE15{slash}MIPI_DPHY_DSI_TX_D0P") (class "Default")
      (node (ref "CON0") (pin "B66") (pinfunction "1AE15/<MIPI_DPHY_DSI_TX_D0P>_B66") (pintype "power_in"))
    )
    (net (code "26") (name "1AE17{slash}SARADC_IN5{slash}1V8") (class "Default")
      (node (ref "CON0") (pin "A11") (pinfunction "1AE17/<SARADC_IN5>/1V8_A11") (pintype "power_in"))
    )
    (net (code "27") (name "1AE19{slash}SARADC_IN2{slash}1V8") (class "Default")
      (node (ref "CON0") (pin "A19") (pinfunction "1AE19/<SARADC_IN2>/1V8_A19") (pintype "passive"))
    )
    (net (code "28") (name "1AE21{slash}HDMI_TX_HPDIN_M0{slash}3V3") (class "Default")
      (node (ref "CON0") (pin "A23") (pinfunction "1AE21/<PCIE0_CLKREQN_M3/HDMI_TX_HPDIN_M0/PWM0_CH1_M1/I2C3_SDA_M3/EDP_TX_HPDIN_M0/UART6_RX_M1/VO_EBC_SDDO17/DSM_AUD_LN_M1/SAI3_SDI_M2/GPIO4_B1_d>/3V3_A23") (pintype "passive"))
    )
    (net (code "29") (name "1AF7{slash}CAN3_RX_M0{slash}1V8") (class "Default")
      (node (ref "CON0") (pin "A6") (pinfunction "1AF7/<SATA0_MPSWIT_M0/CAN3_RX_M0/PWM1_CH2_M1/SPDIF_TX1_M1/ETH1_PTP_REFCLK_M1/GPIO1_D6_d>/1V8_A6") (pintype "passive"))
    )
    (net (code "30") (name "1AF9{slash}ETH1_RXD1_M1{slash}1V8") (class "Default")
      (node (ref "CON0") (pin "A16") (pinfunction "1AF9/<UART7_TX_M0/SAI2_SDO_M0/ETH1_RXD1_M1/GPIO1_D0_d>/1V8_A16") (pintype "passive"))
    )
    (net (code "31") (name "1AF11{slash}ETH1_RXD0_M1{slash}1V8") (class "Default")
      (node (ref "CON0") (pin "A20") (pinfunction "1AF11/<HDMI_TX_SDA_M1/I2C8_SDA_M1/SPI2_CSN1_M1/UART2_RX_M0/PDM_SDI1_M2/ETH1_RXD0_M1/GPIO1_C7_d>/1V8_A20") (pintype "passive"))
    )
    (net (code "32") (name "1AF21{slash}SARADC_IN0_BOOT{slash}MASKROM{slash}PU{slash}1V8") (class "Default")
      (node (ref "CON0") (pin "A5") (pinfunction "1AF21/<SARADC_IN0_BOOT>/1V8_A5") (pintype "power_in"))
    )
    (net (code "33") (name "1B2{slash}UART2_RX_M1{slash}3V3") (class "Default")
      (node (ref "CON0") (pin "C49") (pinfunction "1B2/<I2C4_SDA_M1/SPI3_MISO_M2/UART2_RX_M1/PDM_CLK1_M1/SAI0_LRCK_M2/SPDIF_TX1_M0/VI_CIF_D13/GPIO2_B4_d>/3V3_C49") (pintype "passive"))
    )
    (net (code "34") (name "1B4{slash}ETH0_RXD2{slash}3V3") (class "Default")
      (node (ref "CON0") (pin "C27") (pinfunction "1B4/<PWM2_CH7_M0/SPI3_CSN1_M2/SPI4_CSN0_M2/UART5_CTSN_M1/PDM_SDI0_M1/SAI0_SDO0_M2/SAI1_SDI0_M0/VI_CIF_D8/ETH0_RXD2/GPIO2_C1_d>/3V3_C27") (pintype "power_in"))
    )
    (net (code "35") (name "1B6{slash}ETH0_TXD1{slash}3V3") (class "Default")
      (node (ref "R497") (pin "1") (pinfunction "1_1") (pintype "passive"))
    )
    (net (code "36") (name "1B8{slash}SDMMC0_CMD_M0{slash}3V3") (class "Default")
      (node (ref "CON0") (pin "C63") (pinfunction "1B8/<CAN2_RX_M0/PWM2_CH4_M0/I2C5_SDA_M0/SPI0_CSN0_M1/UART5_RX_M2/SAI3_SDO_M1/SDMMC0_CMD_M0/FSPI1_CSN0_M0/GPIO2_A4_z>/3V3_C63") (pintype "passive"))
    )
    (net (code "37") (name "1B10{slash}MIPI_DPHY_CSI2_RX_D1P") (class "Default")
      (node (ref "CON0") (pin "C48") (pinfunction "1B10/<MIPI_DPHY_CSI2_RX_D1P>_C48") (pintype "passive"))
    )
    (net (code "38") (name "1B12{slash}MIPI_DPHY_CSI3_RX_CLKP") (class "Default")
      (node (ref "CON0") (pin "C54") (pinfunction "1B12/<MIPI_DPHY_CSI3_RX_CLKP>_C54") (pintype "passive"))
    )
    (net (code "39") (name "1B14{slash}MIPI_DPHY_CSI0_RX_D1P") (class "Default")
      (node (ref "CON0") (pin "D44") (pinfunction "1B14/<MIPI_DPHY_CSI0_RX_D1P>_D44") (pintype "passive"))
    )
    (net (code "40") (name "1B16{slash}MIPI_DPHY_CSI1_RX_CLKP") (class "Default")
      (node (ref "CON0") (pin "C66") (pinfunction "1B16/<MIPI_DPHY_CSI1_RX_CLKP>_C66") (pintype "passive"))
    )
    (net (code "41") (name "1B18{slash}USB_DRD0_ID{slash}1V8") (class "Default")
      (node (ref "CON0") (pin "D63") (pinfunction "1B18/<USB_DRD0_ID>/1V8_D63") (pintype "passive"))
      (node (ref "R601") (pin "1") (pinfunction "1_1") (pintype "passive"))
      (node (ref "TP22") (pin "1") (pinfunction "1_1") (pintype "passive"))
    )
    (net (code "42") (name "1C4{slash}ETH0_RXD3{slash}3V3") (class "Default")
      (node (ref "CON0") (pin "C18") (pinfunction "1C4/<SPI4_MISO_M2/UART5_RTSN_M1/PDM_SDI1_M1/SAI1_SDI1_M0/SAI1_SDO3_M0/VI_CIF_D9/ETH0_RXD3/GPIO2_C0_d>/3V3_C18") (pintype "passive"))
    )
    (net (code "43") (name "1C6{slash}ETH0_TXCTL{slash}3V3") (class "Default")
      (node (ref "R494") (pin "2") (pinfunction "2_2") (pintype "passive"))
    )
    (net (code "44") (name "1C8{slash}SDMMC0_CLK_M0{slash}3V3") (class "Default")
      (node (ref "CON0") (pin "C65") (pinfunction "1C8/<CAN2_TX_M0/I2C5_SCL_M0/SPI0_CLK_M1/UART5_TX_M2/TEST_CLK_OUT/SAI3_SCLK_M1/SDMMC0_CLK_M0/FSPI1_CLK_M0/GPIO2_A5_d>/3V3_C65") (pintype "passive"))
    )
    (net (code "45") (name "1C10{slash}MIPI_DPHY_CSI2_RX_D1N") (class "Default")
      (node (ref "CON0") (pin "C50") (pinfunction "1C10/<MIPI_DPHY_CSI2_RX_D1N>_C50") (pintype "passive"))
    )
    (net (code "46") (name "1C12{slash}MIPI_DPHY_CSI3_RX_CLKN") (class "Default")
      (node (ref "CON0") (pin "C56") (pinfunction "1C12/<MIPI_DPHY_CSI3_RX_CLKN>_C56") (pintype "passive"))
    )
    (net (code "47") (name "1C14{slash}MIPI_DPHY_CSI0_RX_D1N") (class "Default")
      (node (ref "CON0") (pin "D42") (pinfunction "1C14/<MIPI_DPHY_CSI0_RX_D1N>_D42") (pintype "passive"))
    )
    (net (code "48") (name "1C16{slash}MIPI_DPHY_CSI1_RX_CLKN") (class "Default")
      (node (ref "CON0") (pin "C68") (pinfunction "1C16/<MIPI_DPHY_CSI1_RX_CLKN>_C68") (pintype "passive"))
    )
    (net (code "49") (name "1C18{slash}USB_DRD0_VBUSDET{slash}3V3") (class "Default")
      (node (ref "CON0") (pin "D53") (pinfunction "1C18/<USB_DRD0_VBUSDET>/3V3_D53") (pintype "passive"))
    )
    (net (code "50") (name "1D1{slash}GPIO2_B0_d{slash}USB_OTG_INTn{slash}3V3") (class "Default")
      (node (ref "CON0") (pin "C37") (pinfunction "1D1/<PWM2_CH5_M0/UART6_RX_M0/SAI0_MCLK_M2/SAI1_MCLK_M0/GPIO2_B0_d>/3V3_C37") (pintype "passive"))
    )
    (net (code "51") (name "1D2{slash}CAN0_RX_M2{slash}3V3") (class "Default")
      (node (ref "CON0") (pin "C41") (pinfunction "1D2/<CAN0_RX_M2/PCIE1_CLKREQN_M2/I2C2_SDA_M2/SPI4_CSN1_M2/UART9_RX_M2/SAI0_SDI2_M2/SAI1_LRCK_M0/VI_CIF_D14/UART6_CTSN_M0/GPIO2_B3_d>/3V3_C41") (pintype "passive"))
    )
    (net (code "52") (name "1D3{slash}UART2_RTSN_M1{slash}3V3") (class "Default")
      (node (ref "CON0") (pin "C51") (pinfunction "1D3/<UART2_RTSN_M1/SPI4_CLK_M2/UART11_TX_M1/PDM_SDI3_M1/SAI1_SDI3_M0/SAI1_SDO1_M0/VI_CIF_D11/ETH0_PPSCLK/GPIO2_B6_d>/3V3_C51") (pintype "power_in"))
    )
    (net (code "53") (name "1D6{slash}ETH0_RXD0{slash}3V3") (class "Default")
      (node (ref "CON0") (pin "C26") (pinfunction "1D6/<SATA30_PORT0_ACTLED_M0/PWM1_CH3_M2/I2C6_SCL_M2/SPI1_CSN0_M1/UART1_TX_M1/VI_CIF_D1/SAI0_SDO0_M0/SDMMC0_PWREN_M1/FSPI1_D1_M1/ETH0_RXD0/GPIO2_D2_d>/3V3_C26") (pintype "passive"))
    )
    (net (code "54") (name "1D8{slash}SDMMC0_D0_M0{slash}3V3") (class "Default")
      (node (ref "CON0") (pin "C67") (pinfunction "1D8/<CAN1_RX_M0/PWM2_CH2_M0/I2C8_SCL_M0/SPI0_MOSI_M1/UART0_RX_M1/UART7_RX_M2/DSM_AUD_LP_M0/SDMMC0_D0_M0/FSPI1_D0_M0/GPIO2_A0_d>/3V3_C67") (pintype "passive"))
    )
    (net (code "55") (name "1H21{slash}PCIE1_REFCLKP") (class "Default")
      (node (ref "CON0") (pin "D20") (pinfunction "1H21/<PCIE1_REFCLKP>_D20") (pintype "passive"))
    )
    (net (code "56") (name "1H22{slash}PCIE1_REFCLKN") (class "Default")
      (node (ref "CON0") (pin "D18") (pinfunction "1H22/<PCIE1_REFCLKN>_D18") (pintype "passive"))
    )
    (net (code "57") (name "1K20{slash}GPIO0_A0_d{slash}USER_KEY2{slash}1V8") (class "Default")
      (node (ref "CON0") (pin "D10") (pinfunction "1K20/<AUPLL_CLK_IN/REF_CLK0_OUT/GPIO0_A0_d>/1V8_D10") (pintype "passive"))
    )
    (net (code "58") (name "1K22{slash}I2C6_SCL_M0{slash}1V8") (class "Default")
      (node (ref "CON0") (pin "D12") (pinfunction "1K22/<I2C6_SCL_M0/CLK0_32K_OUT/CLK_32K_IN/GPIO0_A2_d>/1V8_D12") (pintype "passive"))
      (node (ref "R623") (pin "2") (pinfunction "2_2") (pintype "passive"))
      (node (ref "U1") (pin "4") (pinfunction "A2_4") (pintype "passive"))
    )
    (net (code "59") (name "1K22{slash}I2C6_SCL_M0{slash}3V3") (class "Default")
      (node (ref "R8") (pin "2") (pinfunction "2_2") (pintype "passive"))
      (node (ref "U1") (pin "1") (pinfunction "B2_1") (pintype "passive"))
    )
    (net (code "60") (name "1M20{slash}I2C6_SDA_M0{slash}1V8") (class "Default")
      (node (ref "CON0") (pin "D14") (pinfunction "1M20/<I2C6_SDA_M0/PWR_CTRL3/GPIO0_A5_z>/1V8_D14") (pintype "passive"))
      (node (ref "R622") (pin "2") (pinfunction "2_2") (pintype "passive"))
      (node (ref "U1") (pin "5") (pinfunction "A1_5") (pintype "passive"))
    )
    (net (code "61") (name "1M20{slash}I2C6_SDA_M0{slash}3V3") (class "Default")
      (node (ref "R7") (pin "2") (pinfunction "2_2") (pintype "passive"))
      (node (ref "U1") (pin "8") (pinfunction "B1_8") (pintype "passive"))
    )
    (net (code "62") (name "1M23{slash}I2C1_SDA_M0{slash}1V8") (class "Default")
      (node (ref "CON0") (pin "D4") (pinfunction "1M23/<I2C1_SDA_M0/SPI2_MOSI_M0/GPIO0_B3_z>/1V8_D4") (pintype "passive"))
      (node (ref "R620") (pin "2") (pinfunction "2_2") (pintype "passive"))
      (node (ref "U2") (pin "5") (pinfunction "A1_5") (pintype "passive"))
    )
    (net (code "63") (name "1M23{slash}I2C1_SDA_M0{slash}3V3") (class "Default")
      (node (ref "R3") (pin "2") (pinfunction "2_2") (pintype "passive"))
      (node (ref "U2") (pin "8") (pinfunction "B1_8") (pintype "passive"))
    )
    (net (code "64") (name "1P20{slash}SAI0_SDI0_M1{slash}3V3") (class "Default")
      (node (ref "CON0") (pin "B30") (pinfunction "1P20/<UART11_TX_M0/PDM_SDI0_M0/SAI0_SDI0_M1/SPI0_MOSI_M0/GPIO0_D0_d>/3V3_B30") (pintype "power_in"))
    )
    (net (code "65") (name "1P21{slash}GPIO0_D1_d{slash}POWER_CTRL{slash}3V3") (class "Default")
      (node (ref "CON0") (pin "B28") (pinfunction "1P21/<UART11_RX_M0/PDM_SDI1_M0/SAI0_SDO3_M1/SAI0_SDI1_M1/SPI0_MISO_M0/GPIO0_D1_d>/3V3_B28") (pintype "power_in"))
    )
    (net (code "66") (name "1P22{slash}GPIO0_D2_d{slash}POWER_DECT{slash}3V3") (class "Default")
      (node (ref "CON0") (pin "B26") (pinfunction "1P22/<PWM1_CH5_M0/I2C4_SCL_M0/UART1_CTSN_M0/PDM_SDI2_M0/SAI0_SDO2_M1/SAI0_SDI2_M1/CPUBIG_AVS/GPIO0_D2_d>/3V3_B26") (pintype "passive"))
    )
    (net (code "67") (name "1P23{slash}UART1_RTSN_M0{slash}3V3") (class "Default")
      (node (ref "CON0") (pin "B24") (pinfunction "1P23/<PWM2_CH0_M0/I2C4_SDA_M0/UART1_RTSN_M0/PDM_SDI3_M0/SAI0_SDO1_M1/SAI0_SDI3_M1/GPU_AVS/GPIO0_D3_d>/3V3_B24") (pintype "power_in"))
    )
    (net (code "68") (name "1T20{slash}GPIO0_C4_d{slash}WDOG_WDI{slash}3V3") (class "Default")
      (node (ref "CON0") (pin "B38") (pinfunction "1T20/<PWM0_CH0_M0/UART10_TX_M2/PDM_CLK0_M0/SAI0_MCLK_M1/GPIO0_C4_d>/3V3_B38") (pintype "passive"))
    )
    (net (code "69") (name "1T21{slash}SAI0_SDO0_M1{slash}3V3") (class "Default")
      (node (ref "CON0") (pin "B36") (pinfunction "1T21/<I3C_SDA_PU_M0/UART10_RX_M2/SAI0_SDO0_M1/GPIO0_C5_d>/3V3_B36") (pintype "passive"))
    )
    (net (code "70") (name "1T22{slash}SAI0_SCLK_M1{slash}3V3") (class "Default")
      (node (ref "CON0") (pin "B34") (pinfunction "1T22/<I2C3_SCL_M1/UART8_RTSN_M1/SAI0_SCLK_M1/SPI0_CSN0_M0/GPIO0_C6_d>/3V3_B34") (pintype "power_in"))
    )
    (net (code "71") (name "1T23{slash}SAI0_LRCK_M1{slash}3V3") (class "Default")
      (node (ref "CON0") (pin "B32") (pinfunction "1T23/<I2C3_SDA_M1/UART8_CTSN_M1/SAI0_LRCK_M1/SPI0_CLK_M0/GPIO0_C7_d>/3V3_B32") (pintype "power_in"))
    )
    (net (code "72") (name "1V20{slash}SPI4_CLK_M1{slash}3V3") (class "Default")
      (node (ref "R510") (pin "1") (pinfunction "1_1") (pintype "passive"))
    )
    (net (code "73") (name "1V21{slash}DSMC_DATA8{slash}3V3") (class "Default")
      (node (ref "CON0") (pin "B5") (pinfunction "1V21/<PWM1_CH5_M2/UART3_CTSN_M1/SPDIF_TX0_M3/VO_EBC_SDDO14/VO_LCDC_D14/DSMC_DATA8/ETH1_TXD0_M0/GPIO3_B5_d>/3V3_B5") (pintype "passive"))
    )
    (net (code "74") (name "1V22{slash}DSMC_DATA15{slash}3V3") (class "Default")
      (node (ref "CON0") (pin "B1") (pinfunction "1V22/<PWM1_CH1_M2/SPI2_CSN1_M2/UART1_RTSN_M2/PDM_SDI3_M4/VO_EBC_GDSP/VO_LCDC_D22/DSMC_DATA15/ETH1_MDIO_M0/GPIO3_A5_d>/3V3_B1") (pintype "passive"))
    )
    (net (code "75") (name "1V23{slash}DSMC_DATA14{slash}3V3") (class "Default")
      (node (ref "CON0") (pin "B3") (pinfunction "1V23/<PWM1_CH2_M3/UART10_CTSN_M0/UART1_RX_M2/PDM_SDI2_M4/VO_EBC_GDOE/VO_LCDC_D21/DSMC_DATA14/ETH1_MDC_M0/GPIO3_A6_d>/3V3_B3") (pintype "passive"))
    )
    (net (code "76") (name "1Y20{slash}DSMC_DATA10{slash}3V3") (class "Default")
      (node (ref "CON0") (pin "B21") (pinfunction "1Y20/<I2C8_SCL_M3/UART3_TX_M1/PDM_SDI0_M4/VO_EBC_SDCE0/VO_LCDC_D16/DSMC_DATA10/ETH1_TXCTL_M0/GPIO3_B3_d>/3V3_B21") (pintype "passive"))
    )
    (net (code "77") (name "1Y21{slash}DSMC_DATA13{slash}3V3") (class "Default")
      (node (ref "CON0") (pin "B19") (pinfunction "1Y21/<UART10_RTSN_M0/UART1_TX_M2/PDM_CLK1_M4/VO_EBC_VCOM/VO_LCDC_D20/DSMC_DATA13/ETH1_RXCTL_M0/GPIO3_A7_d>/3V3_B19") (pintype "power_in"))
    )
    (net (code "78") (name "1Y22{slash}DSMC_DATA11{slash}3V3") (class "Default")
      (node (ref "CON0") (pin "B17") (pinfunction "1Y22/<I2C8_SDA_M3/UART3_RX_M1/PDM_SDI1_M4/VO_EBC_SDCE1/VO_LCDC_D17/DSMC_DATA11/ETH1_RXD0_M0/GPIO3_B2_d>/3V3_B17") (pintype "power_in"))
    )
    (net (code "79") (name "1Y23{slash}DSMC_DQS1{slash}3V3") (class "Default")
      (node (ref "CON0") (pin "B41") (pinfunction "1Y23/<PWM0_CH1_M2/SPI3_CSN0_M1/SPDIF_TX1_M3/VO_EBC_SDDO13/VO_LCDC_D13/DSMC_DQS1/ETH1_TXCLK_M0/GPIO3_B6_d>/3V3_B41") (pintype "passive"))
    )
    (net (code "80") (name "2P11{slash}SARADC_IN7{slash}1V8") (class "Default")
      (node (ref "CON0") (pin "A13") (pinfunction "2P11/<SARADC_IN7>/1V8_A13") (pintype "passive"))
    )
    (net (code "81") (name "A4{slash}GPIO2_B7_d{slash}BL_EN{slash}3V3") (class "Default")
      (node (ref "CON0") (pin "C39") (pinfunction "A4/<UART2_CTSN_M1/SPI4_MOSI_M2/UART11_RX_M1/PDM_SDI2_M1/SAI1_SDI2_M0/SAI1_SDO2_M0/VI_CIF_D10/ETH0_PPSTRIG/GPIO2_B7_d>/3V3_C39") (pintype "power_in"))
    )
    (net (code "82") (name "A5{slash}ETH0_TXD2{slash}3V3") (class "Default")
      (node (ref "R499") (pin "1") (pinfunction "1_1") (pintype "passive"))
    )
    (net (code "83") (name "A7{slash}ETH0_RXD1{slash}3V3") (class "Default")
      (node (ref "CON0") (pin "C3") (pinfunction "A7/<PCIE1_CLKREQN_M0/SATA30_PORT1_ACTLED_M0/PWM0_CH0_M2/I2C7_SDA_M1/SPI1_MISO_M1/UART1_RTSN_M1/VI_CIF_D2/PDM_SDI3_M3/SAI0_LRCK_M0/SDMMC0_CLK_M1/FSPI1_D2_M1/ETH0_RXD1/GPIO2_D1_d>/3V3_C3") (pintype "passive"))
    )
    (net (code "84") (name "A8{slash}PWM1_CH2_M2{slash}FAN{slash}3V3") (class "Default")
      (node (ref "CON0") (pin "C55") (pinfunction "A8/<PCIE0_CLKREQN_M0/ISP_FLASH_TRIGOUT_M0/PWM1_CH2_M2/I2C7_SCL_M1/SPI1_MOSI_M1/UART1_CTSN_M1/VI_CIF_D3/PDM_SDI2_M3/SAI0_SCLK_M0/SDMMC0_CMD_M1/FSPI1_D3_M1/ETH0_MCLK/GPIO2_D0_d>/3V3_C55") (pintype "passive"))
    )
    (net (code "85") (name "A10{slash}ETH0_RXCTL{slash}3V3") (class "Default")
      (node (ref "CON0") (pin "C23") (pinfunction "A10/<ISP_PRELIGHT_TRIG_M0/UART11_RX_M2/I2C9_SCL_M2/SPI1_CSN1_M1/UART10_RTSN_M1/VI_CIF_D4/PDM_CLK1_M3/SAI0_MCLK_M0/SDMMC0_D3_M1/FSPI1_D4_M1/ETH0_RXCTL/GPIO2_C7_d>/3V3_C23") (pintype "passive"))
    )
    (net (code "86") (name "A11{slash}GPIO2_C4_d{slash}MIPI_DSI_CAP_TS_nINT{slash}3V3") (class "Default")
      (node (ref "CON0") (pin "C57") (pinfunction "A11/<PWM2_CH4_M2/I2C8_SCL_M2/UART10_TX_M1/VI_CIF_D7/PDM_SDI0_M3/SAI0_SDI2_M0/SDMMC0_D0_M1/FSPI1_D7_M1/ETH_CLK0_25M_OUT/GPIO2_C4_d>/3V3_C57") (pintype "power_in"))
    )
    (net (code "87") (name "A13{slash}MIPI_DPHY_CSI2_RX_D0P") (class "Default")
      (node (ref "CON0") (pin "C30") (pinfunction "A13/<MIPI_DPHY_CSI2_RX_D0P>_C30") (pintype "passive"))
    )
    (net (code "88") (name "A14{slash}MIPI_DPHY_CSI2_RX_CLKP") (class "Default")
      (node (ref "CON0") (pin "C36") (pinfunction "A14/<MIPI_DPHY_CSI2_RX_CLKP>_C36") (pintype "passive"))
    )
    (net (code "89") (name "A16{slash}MIPI_DPHY_CSI2_RX_D2P") (class "Default")
      (node (ref "CON0") (pin "C42") (pinfunction "A16/<MIPI_DPHY_CSI2_RX_D2P/MIPI_DPHY_CSI3_RX_D0P>_C42") (pintype "passive"))
    )
    (net (code "90") (name "A17{slash}MIPI_DPHY_CSI2_RX_D3P") (class "Default")
      (node (ref "CON0") (pin "C60") (pinfunction "A17/<MIPI_DPHY_CSI2_RX_D3P/MIPI_DPHY_CSI3_RX_D1P>_C60") (pintype "passive"))
    )
    (net (code "91") (name "A19{slash}MIPI_DPHY_CSI0_RX_D0P") (class "Default")
      (node (ref "CON0") (pin "D68") (pinfunction "A19/<MIPI_DPHY_CSI0_RX_D0P>_D68") (pintype "passive"))
    )
    (net (code "92") (name "A20{slash}MIPI_DPHY_CSI0_RX_CLKP") (class "Default")
      (node (ref "CON0") (pin "D56") (pinfunction "A20/<MIPI_DPHY_CSI0_RX_CLKP>_D56") (pintype "passive"))
    )
    (net (code "93") (name "A22{slash}MIPI_DPHY_CSI0_RX_D2P") (class "Default")
      (node (ref "CON0") (pin "D62") (pinfunction "A22/<MIPI_DPHY_CSI0_RX_D2P/MIPI_DPHY_CSI1_RX_D0P>_D62") (pintype "passive"))
    )
    (net (code "94") (name "A23{slash}MIPI_DPHY_CSI0_RX_D3P") (class "Default")
      (node (ref "CON0") (pin "D50") (pinfunction "A23/<MIPI_DPHY_CSI0_RX_D3P/MIPI_DPHY_CSI1_RX_D1P>_D50") (pintype "power_in"))
    )
    (net (code "95") (name "A25{slash}USB_DRD0_DM") (class "Default")
      (node (ref "CON0") (pin "D65") (pinfunction "A25/<USB_DRD0_DM>_D65") (pintype "passive"))
    )
    (net (code "96") (name "A26{slash}USB_DRD1_DM") (class "Default")
      (node (ref "CON0") (pin "D57") (pinfunction "A26/<USB_DRD1_DM>_D57") (pintype "passive"))
    )
    (net (code "97") (name "A28{slash}USB_DRD1_ID{slash}1V8") (class "Default")
      (node (ref "CON0") (pin "D55") (pinfunction "A28/<USB_DRD1_ID>/1V8_D55") (pintype "passive"))
      (node (ref "R602") (pin "1") (pinfunction "1_1") (pintype "passive"))
      (node (ref "TP23") (pin "1") (pinfunction "1_1") (pintype "passive"))
    )
    (net (code "98") (name "AA32{slash}UART1_TX_M0{slash}3V3") (class "Default")
      (node (ref "CON0") (pin "B16") (pinfunction "AA32/<PWM1_CH4_M0/I2C2_SCL_M0/UART1_TX_M0/NPU_AVS/GPIO0_B7_d>/3V3_B16") (pintype "power_in"))
    )
    (net (code "99") (name "AB32{slash}UART4_RX_M2{slash}3V3") (class "Default")
      (node (ref "CON0") (pin "B14") (pinfunction "AB32/<PWM1_CH1_M0/I2C1_SDA_M1/UART4_RX_M2/REF_CLK2_OUT/GPIO0_B5_d>/3V3_B14") (pintype "power_in"))
    )
    (net (code "100") (name "AB33{slash}GPIO0_B6_d{slash}LED1{slash}3V3") (class "Default")
      (node (ref "CON0") (pin "B12") (pinfunction "AB33/<PWM1_CH2_M0/SDMMC1_DETN_M1/SDMMC0_PWREN_M0/HDMI_TX_HPDIN_M1/EDP_TX_HPDIN_M1/GPIO0_B6_d>/3V3_B12") (pintype "passive"))
    )
    (net (code "101") (name "AC32{slash}DSMC_DATA2{slash}3V3") (class "Default")
      (node (ref "CON0") (pin "B13") (pinfunction "AC32/<SATA0_CPPOD_M1/SPI1_CLK_M2/UART8_RTSN_M0/VO_EBC_SDDO4/VO_LCDC_D4/DSMC_DATA2/GPIO3_C7_d>/3V3_B13") (pintype "passive"))
    )
    (net (code "102") (name "AC33{slash}UART4_TX_M2{slash}3V3") (class "Default")
      (node (ref "CON0") (pin "B10") (pinfunction "AC33/<PWM1_CH0_M0/I2C1_SCL_M1/UART4_TX_M2/REF_CLK1_OUT/GPIO0_B4_d>/3V3_B10") (pintype "passive"))
    )
    (net (code "103") (name "AD32{slash}SPI4_MISO_M1{slash}3V3") (class "Default")
      (node (ref "CON0") (pin "B11") (pinfunction "AD32/<CAN3_RX_M2/PWM2_CH0_M2/I2C9_SCL_M3/SPI4_MISO_M1/UART4_RTSN_M0/SAI2_SCLK_M1/VO_EBC_SDDO9/VO_LCDC_D9/DSMC_INT1/ETH1_TXD3_M0/GPIO3_C2_d>/3V3_B11") (pintype "tri_state"))
    )
    (net (code "104") (name "AE32{slash}SPI4_MOSI_M1{slash}3V3") (class "Default")
      (node (ref "CON0") (pin "B7") (pinfunction "AE32/<CAN3_TX_M2/PWM2_CH1_M2/I2C9_SDA_M3/SPI4_MOSI_M1/UART4_CTSN_M0/SAI2_LRCK_M1/VO_EBC_SDDO8/VO_LCDC_D8/DSMC_INT3/ETH1_TXD2_M0/GPIO3_C3_d>/3V3_B7") (pintype "passive"))
    )
    (net (code "105") (name "AE33{slash}DSMC_DATA9{slash}3V3") (class "Default")
      (node (ref "CON0") (pin "B23") (pinfunction "AE33/<PWM1_CH4_M3/UART3_RTSN_M1/SPDIF_RX0_M3/VO_EBC_SDDO15/VO_LCDC_D15/DSMC_DATA9/ETH1_TXD1_M0/GPIO3_B4_d>/3V3_B23") (pintype "passive"))
    )
    (net (code "106") (name "AF32{slash}DSMC_CSN0{slash}3V3") (class "Default")
      (node (ref "CON0") (pin "B31") (pinfunction "AF32/<PWM2_CH5_M3/SPI3_CSN1_M1/UART2_CTSN_M2/SAI2_SDO_M1/VO_EBC_SDDO0/VO_LCDC_D0/DSMC_CSN0/ETH1_RXD2_M0/GPIO3_D3_z>/3V3_B31") (pintype "passive"))
    )
    (net (code "107") (name "AF33{slash}SPI4_CSN1_M1{slash}3V3") (class "Default")
      (node (ref "CON0") (pin "B25") (pinfunction "AF33/<PWM2_CH4_M3/SPI4_CSN1_M1/UART2_RTSN_M2/SAI2_SDI_M1/VO_EBC_SDDO1/VO_LCDC_D1/DSMC_CSN3/ETH1_RXD3_M0/GPIO3_D2_z>/3V3_B25") (pintype "passive"))
    )
    (net (code "108") (name "AG32{slash}DSMC_DATA12{slash}3V3") (class "Default")
      (node (ref "CON0") (pin "B35") (pinfunction "AG32/<PWM1_CH3_M3/SPI4_CSN0_M1/UART10_TX_M0/PDM_CLK0_M4/VO_EBC_SDCE2/VO_LCDC_D18/DSMC_DATA12/ETH1_RXD1_M0/GPIO3_B1_d>/3V3_B35") (pintype "passive"))
    )
    (net (code "109") (name "AH32{slash}DSMC_DATA7{slash}3V3") (class "Default")
      (node (ref "CON0") (pin "B37") (pinfunction "AH32/<CAN2_TX_M2/I2C4_SCL_M3/UART9_RTSN_M1/UART2_TX_M2/SAI1_SDO3_M1/VO_EBC_SDDO11/VO_LCDC_D11/DSMC_DATA7/ETH1_PPSCLK_M0/GPIO3_C0_d>/3V3_B37") (pintype "passive"))
    )
    (net (code "110") (name "AH33{slash}DSMC_DATA5{slash}3V3") (class "Default")
      (node (ref "CON0") (pin "B39") (pinfunction "AH33/<SATA0_MPSWIT_M1/CAN0_TX_M3/I2C5_SCL_M3/SPI2_CSN0_M2/UART4_TX_M0/SAI2_MCLK_M1/VO_EBC_SDDO7/VO_LCDC_D7/DSMC_DATA5/GPIO3_C4_d>/3V3_B39") (pintype "passive"))
    )
    (net (code "111") (name "AJ32{slash}DSMC_DATA4{slash}3V3") (class "Default")
      (node (ref "CON0") (pin "B29") (pinfunction "AJ32/<PWM2_CH2_M3/SPI1_MISO_M2/UART8_RX_M0/VO_EBC_SDDO6/VO_LCDC_D6/DSMC_DATA4/GPIO3_C5_d>/3V3_B29") (pintype "passive"))
    )
    (net (code "112") (name "AJ33{slash}DSMC_DATA3{slash}3V3") (class "Default")
      (node (ref "CON0") (pin "B33") (pinfunction "AJ33/<SPI1_MOSI_M2/UART8_TX_M0/VO_EBC_SDDO5/VO_LCDC_D5/DSMC_DATA3/GPIO3_C6_d>/3V3_B33") (pintype "passive"))
    )
    (net (code "113") (name "AK32{slash}DSMC_DQS0{slash}3V3") (class "Default")
      (node (ref "CON0") (pin "B47") (pinfunction "AK32/<CAN2_RX_M2/I2C4_SDA_M3/UART9_CTSN_M1/UART2_RX_M2/SAI1_SDI0_M1/VO_EBC_SDDO12/VO_LCDC_D12/DSMC_DQS0/ETH1_PPSTRIG_M0/GPIO3_B7_d>/3V3_B47") (pintype "passive"))
    )
    (net (code "114") (name "AL32{slash}DSMC_DATA0{slash}3V3") (class "Default")
      (node (ref "CON0") (pin "B49") (pinfunction "AL32/<I2C3_SCL_M2/SPI3_CLK_M1/UART5_RX_M0/SAI1_SDI1_M1/VO_EBC_SDLE/VO_LCDC_DEN/DSMC_DATA0/GPIO3_D4_d>/3V3_B49") (pintype "power_in"))
    )
    (net (code "115") (name "AL33{slash}DSMC_DATA6{slash}3V3") (class "Default")
      (node (ref "CON0") (pin "B51") (pinfunction "AL33/<CAN0_RX_M3/I2C5_SDA_M3/SPI2_MISO_M2/UART4_RX_M0/SAI1_SDO2_M1/VO_EBC_SDDO10/VO_LCDC_D10/DSMC_DATA6/ETH1_PTP_REFCLK_M0/GPIO3_C1_d>/3V3_B51") (pintype "passive"))
    )
    (net (code "116") (name "AM32{slash}DSMC_RESETN{slash}3V3") (class "Default")
      (node (ref "CON0") (pin "B55") (pinfunction "AM32/<SATA1_MPSWIT_M1/PWM2_CH7_M2/UART5_RTSN_M0/SAI1_SDO1_M1/VO_EBC_SDOE/VO_LCDC_CLK/DSMC_RESETN/CAM_CLK0_OUT_M0/GPIO3_D7_d>/3V3_B55") (pintype "passive"))
    )
    (net (code "117") (name "AM33{slash}DSMC_CLKN{slash}3V3") (class "Default")
      (node (ref "R508") (pin "1") (pinfunction "1_1") (pintype "passive"))
    )
    (net (code "118") (name "AN32{slash}CAN1_RX_M1{slash}3V3") (class "Default")
      (node (ref "CON0") (pin "A29") (pinfunction "AN32/<CAN1_RX_M1/PWM2_CH3_M1/I2C6_SDA_M3/SPI4_CLK_M0/UART9_RTSN_M0/VO_EBC_SDDO23/GPIO4_B7_d>/3V3_A29") (pintype "passive"))
    )
    (net (code "119") (name "AP32{slash}GPIO4_B5_d{slash}LED2{slash}3V3") (class "Default")
      (node (ref "CON0") (pin "A27") (pinfunction "AP32/<ISP_FLASH_TRIGOUT_M1/PWM2_CH5_M1/I2C7_SDA_M3/SPI4_MOSI_M0/UART9_RX_M0/VO_EBC_SDDO21/VP0_SYNC_OUT/SATA30_PORT0_ACTLED_M1/GPIO4_B5_d>/3V3_A27") (pintype "passive"))
    )
    (net (code "120") (name "AP33{slash}CAN1_TX_M1{slash}3V3") (class "Default")
      (node (ref "CON0") (pin "A31") (pinfunction "AP33/<PCIE1_CLKREQN_M3/CAN1_TX_M1/PWM2_CH2_M1/I2C6_SCL_M3/SPI4_MISO_M0/UART9_CTSN_M0/VO_EBC_SDDO22/VP1_SYNC_OUT/SATA30_PORT1_ACTLED_M1/GPIO4_B6_d>/3V3_A31") (pintype "passive"))
    )
    (net (code "121") (name "AR13{slash}ETH1_RXD3_M1{slash}1V8") (class "Default")
      (node (ref "CON0") (pin "A24") (pinfunction "AR13/<PWM1_CH1_M1/I2C9_SCL_M1/SPI1_MOSI_M0/SAI4_LRCK_M1/SDMMC1_D1/ETH1_RXD3_M1/GPIO1_B5_d>/1V8_A24") (pintype "passive"))
    )
    (net (code "122") (name "AR14{slash}ETH1_RXD2_M1{slash}1V8") (class "Default")
      (node (ref "CON0") (pin "A22") (pinfunction "AR14/<PCIE1_CLKREQN_M1/PWM1_CH0_M1/I2C9_SDA_M1/SPI1_CLK_M0/SAI4_MCLK_M1/SDMMC1_D0/ETH1_RXD2_M1/GPIO1_B4_d>/1V8_A22") (pintype "passive"))
    )
    (net (code "123") (name "AR15{slash}ETH1_TXCLK_M1{slash}1V8") (class "Default")
      (node (ref "C436") (pin "1") (pinfunction "1_1") (pintype "passive"))
      (node (ref "CON0") (pin "A34") (pinfunction "AR15/<UART3_RX_M2/PDM_CLK0_M2/SDMMC1_CLK/ETH1_TXCLK_M1/GPIO1_C1_d>/1V8_A34") (pintype "passive"))
    )
    (net (code "124") (name "AR16{slash}ETH1_TXD3_M1{slash}1V8") (class "Default")
      (node (ref "R496") (pin "2") (pinfunction "2_2") (pintype "passive"))
    )
    (net (code "125") (name "AR17{slash}CAN2_TX_M1{slash}1V8") (class "Default")
      (node (ref "CON0") (pin "A32") (pinfunction "AR17/<SATA0_CPDET_M0/CAN2_TX_M1/I2C6_SDA_M1/UART4_CTSN_M1/SDMMC1_DETN_M0/ETH1_PPSTRIG_M1/GPIO1_C3_d>/1V8_A32") (pintype "passive"))
    )
    (net (code "126") (name "AR18{slash}CAN3_TX_M0{slash}1V8") (class "Default")
      (node (ref "CON0") (pin "A1") (pinfunction "AR18/<CLK1_32K_OUT/CAN3_TX_M0/I2C5_SDA_M1/SPI2_CLK_M1/UART7_CTSN_M0/PDM_CLK1_M2/SPDIF_TX0_M1/ETH_CLK1_25M_OUT_M1/GPIO1_D5_d>/1V8_A1") (pintype "power_in"))
    )
    (net (code "127") (name "AR20{slash}HDMI_TX_D3N") (class "Default")
      (node (ref "CON0") (pin "A41") (pinfunction "AR20/<HDMI_TX_D3N/EDP_TX_D3N>_A41") (pintype "passive"))
    )
    (net (code "128") (name "AR21{slash}HDMI_TX_D0P") (class "Default")
      (node (ref "CON0") (pin "A49") (pinfunction "AR21/<HDMI_TX_D0P/EDP_TX_D0P>_A49") (pintype "passive"))
    )
    (net (code "129") (name "AR23{slash}HDMI_TX_D1N") (class "Default")
      (node (ref "CON0") (pin "A53") (pinfunction "AR23/<HDMI_TX_D1N/EDP_TX_D1N>_A53") (pintype "passive"))
    )
    (net (code "130") (name "AR24{slash}HDMI_TX_D2P") (class "Default")
      (node (ref "CON0") (pin "A61") (pinfunction "AR24/<HDMI_TX_D2P/EDP_TX_D2P>_A61") (pintype "passive"))
    )
    (net (code "131") (name "AR26{slash}MIPI_DPHY_DSI_TX_D1N") (class "Default")
      (node (ref "CON0") (pin "B62") (pinfunction "AR26/<MIPI_DPHY_DSI_TX_D1N>_B62") (pintype "passive"))
    )
    (net (code "132") (name "AR27{slash}MIPI_DPHY_DSI_TX_CLKN") (class "Default")
      (node (ref "CON0") (pin "B56") (pinfunction "AR27/<MIPI_DPHY_DSI_TX_CLKN>_B56") (pintype "passive"))
    )
    (net (code "133") (name "AR29{slash}MIPI_DPHY_DSI_TX_D2N") (class "Default")
      (node (ref "CON0") (pin "B50") (pinfunction "AR29/<MIPI_DPHY_DSI_TX_D2N>_B50") (pintype "passive"))
    )
    (net (code "134") (name "AR30{slash}MIPI_DPHY_DSI_TX_D3N") (class "Default")
      (node (ref "CON0") (pin "B44") (pinfunction "AR30/<MIPI_DPHY_DSI_TX_D3N>_B44") (pintype "passive"))
    )
    (net (code "135") (name "AR32{slash}HDMI_TX_SDA_M0{slash}3V3") (class "Default")
      (node (ref "CON0") (pin "A35") (pinfunction "AR32/<CAN0_RX_M1/HDMI_TX_SDA_M0/PWM2_CH1_M1/I2C2_SDA_M3/UART6_CTSN_M1/VO_EBC_SDDO19/DSM_AUD_RN_M1/SAI3_SCLK_M2/GPIO4_B3_d>/3V3_A35") (pintype "passive"))
    )
    (net (code "136") (name "AR33{slash}GPIO4_B4_d{slash}HP_DET_L{slash}XL9555_INT1{slash}3V3") (class "Default")
      (node (ref "CON0") (pin "A33") (pinfunction "AR33/<ISP_PRELIGHT_TRIG_M1/PWM2_CH6_M1/I2C7_SCL_M3/SPI4_CSN0_M0/UART9_TX_M0/VO_EBC_SDDO20/SAI3_SDO_M2/GPIO4_B4_d>/3V3_A33") (pintype "passive"))
    )
    (net (code "137") (name "AT14{slash}ETH1_RXCLK_M1{slash}1V8") (class "Default")
      (node (ref "CON0") (pin "A26") (pinfunction "AT14/<PCIE0_CLKREQN_M1/SPI1_MISO_M0/UART3_CTSN_M2/SAI4_SDI_M1/SDMMC1_D2/ETH1_RXCLK_M1/GPIO1_B6_d>/1V8_A26") (pintype "passive"))
    )
    (net (code "138") (name "AT15{slash}ETH1_TXD2_M1{slash}1V8") (class "Default")
      (node (ref "R495") (pin "2") (pinfunction "2_2") (pintype "passive"))
    )
    (net (code "139") (name "AT17{slash}ETH1_TXD0_M1{slash}1V8") (class "Default")
      (node (ref "R502") (pin "2") (pinfunction "2_2") (pintype "passive"))
    )
    (net (code "140") (name "AT18{slash}ETH1_TXD1_M1{slash}1V8") (class "Default")
      (node (ref "R500") (pin "2") (pinfunction "2_2") (pintype "passive"))
    )
    (net (code "141") (name "AT20{slash}HDMI_TX_D3P") (class "Default")
      (node (ref "CON0") (pin "A43") (pinfunction "AT20/<HDMI_TX_D3P/EDP_TX_D3P>_A43") (pintype "passive"))
    )
    (net (code "142") (name "AT21{slash}HDMI_TX_D0N") (class "Default")
      (node (ref "CON0") (pin "A47") (pinfunction "AT21/<HDMI_TX_D0N/EDP_TX_D0N>_A47") (pintype "passive"))
    )
    (net (code "143") (name "AT23{slash}HDMI_TX_D1P") (class "Default")
      (node (ref "CON0") (pin "A55") (pinfunction "AT23/<HDMI_TX_D1P/EDP_TX_D1P>_A55") (pintype "passive"))
    )
    (net (code "144") (name "AT24{slash}HDMI_TX_D2N") (class "Default")
      (node (ref "CON0") (pin "A59") (pinfunction "AT24/<HDMI_TX_D2N/EDP_TX_D2N>_A59") (pintype "passive"))
    )
    (net (code "145") (name "AT26{slash}MIPI_DPHY_DSI_TX_D1P") (class "Default")
      (node (ref "CON0") (pin "B60") (pinfunction "AT26/<MIPI_DPHY_DSI_TX_D1P>_B60") (pintype "passive"))
    )
    (net (code "146") (name "AT27{slash}MIPI_DPHY_DSI_TX_CLKP") (class "Default")
      (node (ref "CON0") (pin "B54") (pinfunction "AT27/<MIPI_DPHY_DSI_TX_CLKP>_B54") (pintype "passive"))
    )
    (net (code "147") (name "AT29{slash}MIPI_DPHY_DSI_TX_D2P") (class "Default")
      (node (ref "CON0") (pin "B48") (pinfunction "AT29/<MIPI_DPHY_DSI_TX_D2P>_B48") (pintype "passive"))
    )
    (net (code "148") (name "AT30{slash}MIPI_DPHY_DSI_TX_D3P") (class "Default")
      (node (ref "CON0") (pin "B42") (pinfunction "AT30/<MIPI_DPHY_DSI_TX_D3P>_B42") (pintype "passive"))
    )
    (net (code "149") (name "AT32{slash}HDMI_TX_SCL_M0{slash}3V3") (class "Default")
      (node (ref "CON0") (pin "A37") (pinfunction "AT32/<CAN0_TX_M1/HDMI_TX_SCL_M0/PWM2_CH0_M1/I2C2_SCL_M3/UART6_RTSN_M1/VO_EBC_SDDO18/DSM_AUD_RP_M1/SAI3_LRCK_M2/GPIO4_B2_d>/3V3_A37") (pintype "passive"))
    )
    (net (code "150") (name "B3{slash}GPIO2_B2_d{slash}MIPI_DSI_BL_PWM{slash}3V3") (class "Default")
      (node (ref "CON0") (pin "C43") (pinfunction "B3/<I2C4_SCL_M1/SPI3_MOSI_M2/UART9_TX_M2/PDM_CLK0_M1/SAI0_SCLK_M2/VI_CIF_D15/UART6_RTSN_M0/GPIO2_B2_d>/3V3_C43") (pintype "passive"))
    )
    (net (code "151") (name "B4{slash}UART2_TX_M1{slash}3V3") (class "Default")
      (node (ref "CON0") (pin "C45") (pinfunction "B4/<PWM2_CH6_M0/SPI3_CLK_M2/UART2_TX_M1/SAI0_SDI0_M2/SAI1_SDO0_M0/VI_CIF_D12/ETH0_PTP_REFCLK/GPIO2_B5_d>/3V3_C45") (pintype "power_in"))
    )
    (net (code "152") (name "B5{slash}ETH0_TXD3{slash}3V3") (class "Default")
      (node (ref "R498") (pin "1") (pinfunction "1_1") (pintype "passive"))
    )
    (net (code "153") (name "B7{slash}ETH0_RXCLK{slash}3V3") (class "Default")
      (node (ref "CON0") (pin "C9") (pinfunction "B7/<CAN1_RX_M3/PWM2_CH3_M2/I2C4_SDA_M2/SPI3_CSN0_M0/UART3_RTSN_M0/VI_CIF_CLKI/SPDIF_TX0_M2/FSPI1_RST/FSPI1_CSN1_M1/ETH0_RXCLK/GPIO2_D7_z>/3V3_C9") (pintype "passive"))
    )
    (net (code "154") (name "B8{slash}ETH0_TXCLK{slash}3V3") (class "Default")
      (node (ref "C437") (pin "1") (pinfunction "1_1") (pintype "passive"))
      (node (ref "CON0") (pin "C25") (pinfunction "B8/<MIPI_TE_M1/CAN1_TX_M3/PWM2_CH2_M2/I2C4_SCL_M2/SPI3_MISO_M0/UART3_CTSN_M0/VI_CIF_CLKO/SPDIF_RX0_M2/SAI0_SDI3_M0/CAM_CLK2_OUT_M1/FSPI1_CSN0_M1/ETH0_TXCLK/GPIO2_D6_z>/3V3_C25") (pintype "passive"))
    )
    (net (code "155") (name "B9{slash}ETH0_MDC{slash}3V3") (class "Default")
      (node (ref "R506") (pin "2") (pinfunction "2_2") (pintype "passive"))
    )
    (net (code "156") (name "B10{slash}ETH0_MDIO{slash}3V3") (class "Default")
      (node (ref "CON0") (pin "C12") (pinfunction "B10/<PWM2_CH5_M2/I2C8_SDA_M2/UART10_RX_M1/VI_CIF_D6/PDM_CLK0_M3/SAI0_SDI1_M0/SDMMC0_D1_M1/FSPI1_D6_M1/ETH0_MDIO/GPIO2_C5_d>/3V3_C12") (pintype "passive"))
    )
    (net (code "157") (name "B11{slash}SDMMC0_D2_M0{slash}JTAG_TCK_M0{slash}3V3") (class "Default")
      (node (ref "CON0") (pin "C59") (pinfunction "B11/<CAN0_RX_M0/JTAG_TCK_M0/SPI0_CSN1_M1/UART5_RTSN_M2/SAI3_LRCK_M1/DSM_AUD_RP_M0/SDMMC0_D2_M0/FSPI1_D2_M0/GPIO2_A2_d>/3V3_C59") (pintype "passive"))
    )
    (net (code "158") (name "B13{slash}MIPI_DPHY_CSI2_RX_D0N") (class "Default")
      (node (ref "CON0") (pin "C32") (pinfunction "B13/<MIPI_DPHY_CSI2_RX_D0N>_C32") (pintype "passive"))
    )
    (net (code "159") (name "B14{slash}MIPI_DPHY_CSI2_RX_CLKN") (class "Default")
      (node (ref "CON0") (pin "C38") (pinfunction "B14/<MIPI_DPHY_CSI2_RX_CLKN>_C38") (pintype "passive"))
    )
    (net (code "160") (name "B16{slash}MIPI_DPHY_CSI2_RX_D2N") (class "Default")
      (node (ref "CON0") (pin "C44") (pinfunction "B16/<MIPI_DPHY_CSI2_RX_D2N/MIPI_DPHY_CSI3_RX_D0N>_C44") (pintype "passive"))
    )
    (net (code "161") (name "B17{slash}MIPI_DPHY_CSI2_RX_D3N") (class "Default")
      (node (ref "CON0") (pin "C62") (pinfunction "B17/<MIPI_DPHY_CSI2_RX_D3N/MIPI_DPHY_CSI3_RX_D1N>_C62") (pintype "passive"))
    )
    (net (code "162") (name "B19{slash}MIPI_DPHY_CSI0_RX_D0N") (class "Default")
      (node (ref "CON0") (pin "D66") (pinfunction "B19/<MIPI_DPHY_CSI0_RX_D0N>_D66") (pintype "passive"))
    )
    (net (code "163") (name "B20{slash}MIPI_DPHY_CSI0_RX_CLKN") (class "Default")
      (node (ref "CON0") (pin "D54") (pinfunction "B20/<MIPI_DPHY_CSI0_RX_CLKN>_D54") (pintype "passive"))
    )
    (net (code "164") (name "B22{slash}MIPI_DPHY_CSI0_RX_D2N") (class "Default")
      (node (ref "CON0") (pin "D60") (pinfunction "B22/<MIPI_DPHY_CSI0_RX_D2N/MIPI_DPHY_CSI1_RX_D0N>_D60") (pintype "passive"))
    )
    (net (code "165") (name "B23{slash}MIPI_DPHY_CSI0_RX_D3N") (class "Default")
      (node (ref "CON0") (pin "D48") (pinfunction "B23/<MIPI_DPHY_CSI0_RX_D3N/MIPI_DPHY_CSI1_RX_D1N>_D48") (pintype "power_in"))
    )
    (net (code "166") (name "B25{slash}USB_DRD0_DP") (class "Default")
      (node (ref "CON0") (pin "D67") (pinfunction "B25/<USB_DRD0_DP>_D67") (pintype "passive"))
    )
    (net (code "167") (name "B26{slash}USB_DRD1_DP") (class "Default")
      (node (ref "CON0") (pin "D59") (pinfunction "B26/<USB_DRD1_DP>_D59") (pintype "passive"))
    )
    (net (code "168") (name "B28{slash}USB_DRD1_VBUSDET{slash}3V3") (class "Default")
      (node (ref "CON0") (pin "D61") (pinfunction "B28/<USB_DRD1_VBUSDET>/3V3_D61") (pintype "passive"))
    )
    (net (code "169") (name "D32{slash}USB_DRD0_SSRXN") (class "Default")
      (node (ref "C440") (pin "1") (pinfunction "1_1") (pintype "passive"))
    )
    (net (code "170") (name "D33{slash}USB_DRD0_SSRXP") (class "Default")
      (node (ref "C441") (pin "1") (pinfunction "1_1") (pintype "passive"))
    )
    (net (code "171") (name "E32{slash}USB_DRD0_SSTXP") (class "Default")
      (node (ref "CON0") (pin "D37") (pinfunction "E32/<PCIE0_TXP_M0/SATA0_TXP_M0/USB_DRD0_SSTXP>_D37") (pintype "passive"))
    )
    (net (code "172") (name "E33{slash}USB_DRD0_SSTXN") (class "Default")
      (node (ref "CON0") (pin "D35") (pinfunction "E33/<PCIE0_TXN_M0/SATA0_TXN_M0/USB_DRD0_SSTXN>_D35") (pintype "passive"))
    )
    (net (code "173") (name "G32{slash}USB_DRD1_SSTXP") (class "Default")
      (node (ref "CON0") (pin "D31") (pinfunction "G32/<PCIE0_TXP_M1/SATA0_TXP_M1/USB_DRD1_SSTXP>_D31") (pintype "passive"))
    )
    (net (code "174") (name "G33{slash}USB_DRD1_SSTXN") (class "Default")
      (node (ref "CON0") (pin "D29") (pinfunction "G33/<PCIE0_TXN_M1/SATA0_TXN_M1/USB_DRD1_SSTXN>_D29") (pintype "passive"))
    )
    (net (code "175") (name "GND") (class "Default")
      (node (ref "C1") (pin "2") (pinfunction "2_2") (pintype "passive"))
      (node (ref "C10") (pin "2") (pinfunction "2_2") (pintype "passive"))
      (node (ref "C11") (pin "2") (pinfunction "2_2") (pintype "passive"))
      (node (ref "C12") (pin "2") (pinfunction "2_2") (pintype "passive"))
      (node (ref "C13") (pin "2") (pinfunction "2_2") (pintype "passive"))
      (node (ref "C2") (pin "2") (pinfunction "2_2") (pintype "passive"))
      (node (ref "C3") (pin "2") (pinfunction "2_2") (pintype "passive"))
      (node (ref "C436") (pin "2") (pinfunction "2_2") (pintype "passive"))
      (node (ref "C437") (pin "2") (pinfunction "2_2") (pintype "passive"))
      (node (ref "C8") (pin "2") (pinfunction "2_2") (pintype "passive"))
      (node (ref "C9") (pin "2") (pinfunction "2_2") (pintype "passive"))
      (node (ref "CON0") (pin "A2") (pinfunction "GND_A2") (pintype "power_in"))
      (node (ref "CON0") (pin "A25") (pinfunction "GND_A25") (pintype "power_in"))
      (node (ref "CON0") (pin "A28") (pinfunction "GND_A28") (pintype "power_in"))
      (node (ref "CON0") (pin "A39") (pinfunction "GND_A39") (pintype "power_in"))
      (node (ref "CON0") (pin "A42") (pinfunction "GND_A42") (pintype "power_in"))
      (node (ref "CON0") (pin "A45") (pinfunction "GND_A45") (pintype "power_in"))
      (node (ref "CON0") (pin "A51") (pinfunction "GND_A51") (pintype "power_in"))
      (node (ref "CON0") (pin "A57") (pinfunction "GND_A57") (pintype "power_in"))
      (node (ref "CON0") (pin "A62") (pinfunction "GND_A62") (pintype "power_in"))
      (node (ref "CON0") (pin "A63") (pinfunction "GND_A63") (pintype "power_in"))
      (node (ref "CON0") (pin "A69") (pinfunction "GND_A69") (pintype "power_in"))
      (node (ref "CON0") (pin "A70") (pinfunction "GND_A70") (pintype "power_in"))
      (node (ref "CON0") (pin "A8") (pinfunction "GND_A8") (pintype "power_in"))
      (node (ref "CON0") (pin "B2") (pinfunction "GND_B2") (pintype "power_in"))
      (node (ref "CON0") (pin "B22") (pinfunction "GND_B22") (pintype "power_in"))
      (node (ref "CON0") (pin "B27") (pinfunction "GND_B27") (pintype "power_in"))
      (node (ref "CON0") (pin "B40") (pinfunction "GND_B40") (pintype "power_in"))
      (node (ref "CON0") (pin "B45") (pinfunction "GND_B45") (pintype "power_in"))
      (node (ref "CON0") (pin "B46") (pinfunction "GND_B46") (pintype "power_in"))
      (node (ref "CON0") (pin "B52") (pinfunction "GND_B52") (pintype "power_in"))
      (node (ref "CON0") (pin "B58") (pinfunction "GND_B58") (pintype "power_in"))
      (node (ref "CON0") (pin "B63") (pinfunction "GND_B63") (pintype "power_in"))
      (node (ref "CON0") (pin "B64") (pinfunction "GND_B64") (pintype "power_in"))
      (node (ref "CON0") (pin "B69") (pinfunction "GND_B69") (pintype "power_in"))
      (node (ref "CON0") (pin "B70") (pinfunction "GND_B70") (pintype "power_in"))
      (node (ref "CON0") (pin "B9") (pinfunction "GND_B9") (pintype "power_in"))
      (node (ref "CON0") (pin "C1") (pinfunction "GND_C1") (pintype "power_in"))
      (node (ref "CON0") (pin "C10") (pinfunction "GND_C10") (pintype "power_in"))
      (node (ref "CON0") (pin "C11") (pinfunction "GND_C11") (pintype "power_in"))
      (node (ref "CON0") (pin "C13") (pinfunction "GND_C13") (pintype "power_in"))
      (node (ref "CON0") (pin "C15") (pinfunction "GND_C15") (pintype "power_in"))
      (node (ref "CON0") (pin "C16") (pinfunction "GND_C16") (pintype "power_in"))
      (node (ref "CON0") (pin "C17") (pinfunction "GND_C17") (pintype "power_in"))
      (node (ref "CON0") (pin "C19") (pinfunction "GND_C19") (pintype "power_in"))
      (node (ref "CON0") (pin "C2") (pinfunction "GND_C2") (pintype "power_in"))
      (node (ref "CON0") (pin "C21") (pinfunction "GND_C21") (pintype "power_in"))
      (node (ref "CON0") (pin "C28") (pinfunction "GND_C28") (pintype "power_in"))
      (node (ref "CON0") (pin "C29") (pinfunction "GND_C29") (pintype "power_in"))
      (node (ref "CON0") (pin "C31") (pinfunction "GND_C31") (pintype "power_in"))
      (node (ref "CON0") (pin "C33") (pinfunction "GND_C33") (pintype "power_in"))
      (node (ref "CON0") (pin "C34") (pinfunction "GND_C34") (pintype "power_in"))
      (node (ref "CON0") (pin "C35") (pinfunction "GND_C35") (pintype "power_in"))
      (node (ref "CON0") (pin "C4") (pinfunction "GND_C4") (pintype "power_in"))
      (node (ref "CON0") (pin "C40") (pinfunction "GND_C40") (pintype "power_in"))
      (node (ref "CON0") (pin "C46") (pinfunction "GND_C46") (pintype "power_in"))
      (node (ref "CON0") (pin "C52") (pinfunction "GND_C52") (pintype "power_in"))
      (node (ref "CON0") (pin "C53") (pinfunction "GND_C53") (pintype "power_in"))
      (node (ref "CON0") (pin "C58") (pinfunction "GND_C58") (pintype "power_in"))
      (node (ref "CON0") (pin "C6") (pinfunction "GND_C6") (pintype "power_in"))
      (node (ref "CON0") (pin "C64") (pinfunction "GND_C64") (pintype "power_in"))
      (node (ref "CON0") (pin "C70") (pinfunction "GND_C70") (pintype "power_in"))
      (node (ref "CON0") (pin "C8") (pinfunction "GND_C8") (pintype "power_in"))
      (node (ref "CON0") (pin "D11") (pinfunction "GND_D11") (pintype "power_in"))
      (node (ref "CON0") (pin "D16") (pinfunction "GND_D16") (pintype "power_in"))
      (node (ref "CON0") (pin "D21") (pinfunction "GND_D21") (pintype "power_in"))
      (node (ref "CON0") (pin "D22") (pinfunction "GND_D22") (pintype "power_in"))
      (node (ref "CON0") (pin "D27") (pinfunction "GND_D27") (pintype "power_in"))
      (node (ref "CON0") (pin "D28") (pinfunction "GND_D28") (pintype "power_in"))
      (node (ref "CON0") (pin "D33") (pinfunction "GND_D33") (pintype "power_in"))
      (node (ref "CON0") (pin "D34") (pinfunction "GND_D34") (pintype "power_in"))
      (node (ref "CON0") (pin "D39") (pinfunction "GND_D39") (pintype "power_in"))
      (node (ref "CON0") (pin "D40") (pinfunction "GND_D40") (pintype "power_in"))
      (node (ref "CON0") (pin "D45") (pinfunction "GND_D45") (pintype "power_in"))
      (node (ref "CON0") (pin "D46") (pinfunction "GND_D46") (pintype "power_in"))
      (node (ref "CON0") (pin "D51") (pinfunction "GND_D51") (pintype "power_in"))
      (node (ref "CON0") (pin "D52") (pinfunction "GND_D52") (pintype "power_in"))
      (node (ref "CON0") (pin "D58") (pinfunction "GND_D58") (pintype "power_in"))
      (node (ref "CON0") (pin "D64") (pinfunction "GND_D64") (pintype "power_in"))
      (node (ref "CON0") (pin "D69") (pinfunction "GND_D69") (pintype "power_in"))
      (node (ref "CON0") (pin "D7") (pinfunction "GND_D7") (pintype "power_in"))
      (node (ref "CON0") (pin "D70") (pinfunction "GND_D70") (pintype "power_in"))
      (node (ref "CON0") (pin "D9") (pinfunction "GND_D9") (pintype "power_in"))
      (node (ref "CON0") (pin "H1") (pinfunction "H1_H1") (pintype "passive"))
      (node (ref "CON0") (pin "H2") (pinfunction "H2_H2") (pintype "passive"))
      (node (ref "CON0") (pin "H3") (pinfunction "H3_H3") (pintype "passive"))
      (node (ref "CON0") (pin "H4") (pinfunction "H4_H4") (pintype "passive"))
      (node (ref "U1") (pin "2") (pinfunction "GND_2") (pintype "passive"))
      (node (ref "U2") (pin "2") (pinfunction "GND_2") (pintype "passive"))
    )
    (net (code "176") (name "H32{slash}USB_DRD1_SSRXP") (class "Default")
      (node (ref "C439") (pin "1") (pinfunction "1_1") (pintype "passive"))
    )
    (net (code "177") (name "H33{slash}USB_DRD1_SSRXN") (class "Default")
      (node (ref "C438") (pin "1") (pinfunction "1_1") (pintype "passive"))
    )
    (net (code "178") (name "K32{slash}PCIE1_RXN") (class "Default")
      (node (ref "CON0") (pin "D30") (pinfunction "K32/<PCIE1_RXN/SATA1_RXN>_D30") (pintype "passive"))
    )
    (net (code "179") (name "K33{slash}PCIE1_RXP") (class "Default")
      (node (ref "CON0") (pin "D32") (pinfunction "K33/<PCIE1_RXP/SATA1_RXP>_D32") (pintype "passive"))
    )
    (net (code "180") (name "L32{slash}PCIE1_TXN") (class "Default")
      (node (ref "CON0") (pin "D24") (pinfunction "L32/<PCIE1_TXN/SATA1_TXN>_D24") (pintype "passive"))
    )
    (net (code "181") (name "L33{slash}PCIE1_TXP") (class "Default")
      (node (ref "CON0") (pin "D26") (pinfunction "L33/<PCIE1_TXP/SATA1_TXP>_D26") (pintype "power_in"))
    )
    (net (code "182") (name "Net-(CON0A-1AD9{slash}<SATA1_CPDET_M0{slash}PWM1_CH3_M1{slash}I3C_SCL_M1{slash}SAI2_LRCK_M0{slash}ETH1_MDC_M1{slash}GPIO1_D2_d>{slash}1V8)") (class "Default")
      (node (ref "CON0") (pin "A12") (pinfunction "1AD9/<SATA1_CPDET_M0/PWM1_CH3_M1/I3C_SCL_M1/SAI2_LRCK_M0/ETH1_MDC_M1/GPIO1_D2_d>/1V8_A12") (pintype "passive"))
      (node (ref "R505") (pin "1") (pinfunction "1_1") (pintype "passive"))
    )
    (net (code "183") (name "Net-(CON0A-1AE7{slash}<HDMI_TX_SCL_M1{slash}I2C8_SCL_M1{slash}SPI2_CSN0_M1{slash}UART2_TX_M0{slash}PDM_SDI0_M2{slash}ETH1_TXCTL_M1{slash}GPIO1_C6_d>{slash}1V8)") (class "Default")
      (node (ref "CON0") (pin "A10") (pinfunction "1AE7/<HDMI_TX_SCL_M1/I2C8_SCL_M1/SPI2_CSN0_M1/UART2_TX_M0/PDM_SDI0_M2/ETH1_TXCTL_M1/GPIO1_C6_d>/1V8_A10") (pintype "passive"))
      (node (ref "R501") (pin "1") (pinfunction "1_1") (pintype "passive"))
    )
    (net (code "184") (name "Net-(CON0A-AR16{slash}<PWM0_CH0_M1{slash}SPI1_CSN1_M0{slash}UART3_TX_M2{slash}PDM_SDI2_M2{slash}SAI4_SCLK_M1{slash}SDMMC1_CMD{slash}ETH1_TXD3_M1{slash}GPIO1_C0_d>{slash}1V8)") (class "Default")
      (node (ref "CON0") (pin "A36") (pinfunction "AR16/<PWM0_CH0_M1/SPI1_CSN1_M0/UART3_TX_M2/PDM_SDI2_M2/SAI4_SCLK_M1/SDMMC1_CMD/ETH1_TXD3_M1/GPIO1_C0_d>/1V8_A36") (pintype "passive"))
      (node (ref "R496") (pin "1") (pinfunction "1_1") (pintype "passive"))
    )
    (net (code "185") (name "Net-(CON0A-AT15{slash}<SPI1_CSN0_M0{slash}UART3_RTSN_M2{slash}SAI4_SDO_M1{slash}SDMMC1_D3{slash}ETH1_TXD2_M1{slash}GPIO1_B7_d>{slash}1V8)") (class "Default")
      (node (ref "CON0") (pin "A30") (pinfunction "AT15/<SPI1_CSN0_M0/UART3_RTSN_M2/SAI4_SDO_M1/SDMMC1_D3/ETH1_TXD2_M1/GPIO1_B7_d>/1V8_A30") (pintype "passive"))
      (node (ref "R495") (pin "1") (pinfunction "1_1") (pintype "passive"))
    )
    (net (code "186") (name "Net-(CON0A-AT17{slash}<SPI2_MOSI_M1{slash}UART4_TX_M1{slash}UART2_RTSN_M0{slash}ETH1_TXD0_M1{slash}GPIO1_C4_d>{slash}1V8)") (class "Default")
      (node (ref "CON0") (pin "A38") (pinfunction "AT17/<SPI2_MOSI_M1/UART4_TX_M1/UART2_RTSN_M0/ETH1_TXD0_M1/GPIO1_C4_d>/1V8_A38") (pintype "passive"))
      (node (ref "R502") (pin "1") (pinfunction "1_1") (pintype "passive"))
    )
    (net (code "187") (name "Net-(CON0A-AT18{slash}<SPI2_MISO_M1{slash}UART4_RX_M1{slash}UART2_CTSN_M0{slash}ETH1_TXD1_M1{slash}GPIO1_C5_d>{slash}1V8)") (class "Default")
      (node (ref "CON0") (pin "A40") (pinfunction "AT18/<SPI2_MISO_M1/UART4_RX_M1/UART2_CTSN_M0/ETH1_TXD1_M1/GPIO1_C5_d>/1V8_A40") (pintype "passive"))
      (node (ref "R500") (pin "1") (pinfunction "1_1") (pintype "passive"))
    )
    (net (code "188") (name "Net-(CON0B-1AB20{slash}<I2C3_SDA_M2{slash}SPI3_MISO_M1{slash}UART5_TX_M0{slash}SAI1_SDI2_M1{slash}VO_EBC_GDCLK{slash}VO_LCDC_HSYNC{slash}DSMC_CLKP{slash}GPIO3_D5_d>{slash}3V3)") (class "Default")
      (node (ref "CON0") (pin "B61") (pinfunction "1AB20/<I2C3_SDA_M2/SPI3_MISO_M1/UART5_TX_M0/SAI1_SDI2_M1/VO_EBC_GDCLK/VO_LCDC_HSYNC/DSMC_CLKP/GPIO3_D5_d>/3V3_B61") (pintype "passive"))
      (node (ref "R509") (pin "2") (pinfunction "2_2") (pintype "passive"))
    )
    (net (code "189") (name "Net-(CON0B-1V20{slash}<SPI4_CLK_M1{slash}VO_EBC_SDDO2{slash}VO_LCDC_D2{slash}DSMC_CSN2{slash}ETH1_RXCLK_M0{slash}GPIO3_D1_z>{slash}3V3)") (class "Default")
      (node (ref "CON0") (pin "B15") (pinfunction "1V20/<SPI4_CLK_M1/VO_EBC_SDDO2/VO_LCDC_D2/DSMC_CSN2/ETH1_RXCLK_M0/GPIO3_D1_z>/3V3_B15") (pintype "passive"))
      (node (ref "R510") (pin "2") (pinfunction "2_2") (pintype "passive"))
    )
    (net (code "190") (name "Net-(CON0B-AM33{slash}<PWM2_CH6_M2{slash}SPI3_MOSI_M1{slash}UART5_CTSN_M0{slash}SAI1_SDI3_M1{slash}VO_EBC_SDCLK{slash}VO_LCDC_VSYNC{slash}DSMC_CLKN{slash}GPIO3_D6_d>{slash}3V3)") (class "Default")
      (node (ref "CON0") (pin "B53") (pinfunction "AM33/<PWM2_CH6_M2/SPI3_MOSI_M1/UART5_CTSN_M0/SAI1_SDI3_M1/VO_EBC_SDCLK/VO_LCDC_VSYNC/DSMC_CLKN/GPIO3_D6_d>/3V3_B53") (pintype "passive"))
      (node (ref "R508") (pin "2") (pinfunction "2_2") (pintype "passive"))
    )
    (net (code "191") (name "Net-(CON0C-1A6{slash}<CAN3_TX_M1{slash}I2C5_SCL_M2{slash}SPI3_CLK_M0{slash}UART3_TX_M0{slash}VI_CIF_HREF{slash}SAI0_SDO2_M0{slash}CAM_CLK0_OUT_M1{slash}FSPI1_DQS_M1{slash}ETH0_TXD0{slash}GPIO2_D4_d>{slash}3V3)") (class "Default")
      (node (ref "CON0") (pin "C20") (pinfunction "1A6/<CAN3_TX_M1/I2C5_SCL_M2/SPI3_CLK_M0/UART3_TX_M0/VI_CIF_HREF/SAI0_SDO2_M0/CAM_CLK0_OUT_M1/FSPI1_DQS_M1/ETH0_TXD0/GPIO2_D4_d>/3V3_C20") (pintype "passive"))
      (node (ref "R493") (pin "1") (pinfunction "1_1") (pintype "passive"))
    )
    (net (code "192") (name "Net-(CON0C-1B6{slash}<CAN3_RX_M1{slash}I2C5_SDA_M2{slash}SPI3_MOSI_M0{slash}UART3_RX_M0{slash}VI_CIF_VSYNC{slash}SPDIF_TX1_M2{slash}SAI0_SDO3_M0{slash}CAM_CLK1_OUT_M1{slash}FSPI1_CLK_M1{slash}ETH0_TXD1{slash}GPIO2_D5_d>{slash}3V3)") (class "Default")
      (node (ref "CON0") (pin "C22") (pinfunction "1B6/<CAN3_RX_M1/I2C5_SDA_M2/SPI3_MOSI_M0/UART3_RX_M0/VI_CIF_VSYNC/SPDIF_TX1_M2/SAI0_SDO3_M0/CAM_CLK1_OUT_M1/FSPI1_CLK_M1/ETH0_TXD1/GPIO2_D5_d>/3V3_C22") (pintype "passive"))
      (node (ref "R497") (pin "2") (pinfunction "2_2") (pintype "passive"))
    )
    (net (code "193") (name "Net-(CON0C-1C6{slash}<PWM1_CH4_M2{slash}I2C6_SDA_M2{slash}SPI1_CLK_M1{slash}UART1_RX_M1{slash}VI_CIF_D0{slash}SAI0_SDI0_M0{slash}SDMMC0_DETN_M1{slash}FSPI1_D0_M1{slash}ETH0_TXCTL{slash}GPIO2_D3_d>{slash}3V3)") (class "Default")
      (node (ref "CON0") (pin "C24") (pinfunction "1C6/<PWM1_CH4_M2/I2C6_SDA_M2/SPI1_CLK_M1/UART1_RX_M1/VI_CIF_D0/SAI0_SDI0_M0/SDMMC0_DETN_M1/FSPI1_D0_M1/ETH0_TXCTL/GPIO2_D3_d>/3V3_C24") (pintype "passive"))
      (node (ref "R494") (pin "1") (pinfunction "1_1") (pintype "passive"))
    )
    (net (code "194") (name "Net-(CON0C-A5{slash}<CAN1_RX_M2{slash}MIPI_TE_M0{slash}I2C3_SDA_M0{slash}UART5_RX_M1{slash}SAI0_SDI3_M2{slash}SPDIF_RX0_M0{slash}ETH0_TXD2{slash}GPIO2_C2_d>{slash}3V3)") (class "Default")
      (node (ref "CON0") (pin "C5") (pinfunction "A5/<CAN1_RX_M2/MIPI_TE_M0/I2C3_SDA_M0/UART5_RX_M1/SAI0_SDI3_M2/SPDIF_RX0_M0/ETH0_TXD2/GPIO2_C2_d>/3V3_C5") (pintype "passive"))
      (node (ref "R499") (pin "2") (pinfunction "2_2") (pintype "passive"))
    )
    (net (code "195") (name "Net-(CON0C-B5{slash}<CAN1_TX_M2{slash}PCIE0_CLKREQN_M2{slash}I2C3_SCL_M0{slash}UART5_TX_M1{slash}SPDIF_TX0_M0{slash}ETH0_TXD3{slash}GPIO2_C3_d>{slash}3V3)") (class "Default")
      (node (ref "CON0") (pin "C7") (pinfunction "B5/<CAN1_TX_M2/PCIE0_CLKREQN_M2/I2C3_SCL_M0/UART5_TX_M1/SPDIF_TX0_M0/ETH0_TXD3/GPIO2_C3_d>/3V3_C7") (pintype "passive"))
      (node (ref "R498") (pin "2") (pinfunction "2_2") (pintype "passive"))
    )
    (net (code "196") (name "Net-(CON0C-B9{slash}<UART11_TX_M2{slash}I2C9_SDA_M2{slash}SPI3_CSN1_M0{slash}UART10_CTSN_M1{slash}VI_CIF_D5{slash}PDM_SDI1_M3{slash}SAI0_SDO1_M0{slash}SDMMC0_D2_M1{slash}FSPI1_D5_M1{slash}ETH0_MDC{slash}GPIO2_C6_d>{slash}3V3)") (class "Default")
      (node (ref "CON0") (pin "C14") (pinfunction "B9/<UART11_TX_M2/I2C9_SDA_M2/SPI3_CSN1_M0/UART10_CTSN_M1/VI_CIF_D5/PDM_SDI1_M3/SAI0_SDO1_M0/SDMMC0_D2_M1/FSPI1_D5_M1/ETH0_MDC/GPIO2_C6_d>/3V3_C14") (pintype "passive"))
      (node (ref "R506") (pin "1") (pinfunction "1_1") (pintype "passive"))
    )
    (net (code "197") (name "Net-(CON0D-1D21{slash}<PCIE0_REFCLKP_M0>)") (class "Default")
      (node (ref "CON0") (pin "D49") (pinfunction "1D21/<PCIE0_REFCLKP_M0>_D49") (pintype "passive"))
      (node (ref "TP19") (pin "1") (pinfunction "1_1") (pintype "passive"))
    )
    (net (code "198") (name "Net-(CON0D-1D22{slash}<PCIE0_REFCLKN_M0>)") (class "Default")
      (node (ref "CON0") (pin "D47") (pinfunction "1D22/<PCIE0_REFCLKN_M0>_D47") (pintype "passive"))
      (node (ref "TP18") (pin "1") (pinfunction "1_1") (pintype "passive"))
    )
    (net (code "199") (name "Net-(CON0D-1F21{slash}<PCIE0_REFCLKP_M1>)") (class "Default")
      (node (ref "CON0") (pin "D38") (pinfunction "1F21/<PCIE0_REFCLKP_M1>_D38") (pintype "passive"))
      (node (ref "TP21") (pin "1") (pinfunction "1_1") (pintype "passive"))
    )
    (net (code "200") (name "Net-(CON0D-1F22{slash}<PCIE0_REFCLKN_M1>)") (class "Default")
      (node (ref "CON0") (pin "D36") (pinfunction "1F22/<PCIE0_REFCLKN_M1>_D36") (pintype "passive"))
      (node (ref "TP20") (pin "1") (pinfunction "1_1") (pintype "passive"))
    )
    (net (code "201") (name "Net-(CON0D-D32{slash}<PCIE0_RXN_M0{slash}SATA0_RXN_M0{slash}USB_DRD0_SSRXN>)") (class "Default")
      (node (ref "C440") (pin "2") (pinfunction "2_2") (pintype "passive"))
      (node (ref "CON0") (pin "D41") (pinfunction "D32/<PCIE0_RXN_M0/SATA0_RXN_M0/USB_DRD0_SSRXN>_D41") (pintype "passive"))
    )
    (net (code "202") (name "Net-(CON0D-D33{slash}<PCIE0_RXP_M0{slash}SATA0_RXP_M0{slash}USB_DRD0_SSRXP>)") (class "Default")
      (node (ref "C441") (pin "2") (pinfunction "2_2") (pintype "passive"))
      (node (ref "CON0") (pin "D43") (pinfunction "D33/<PCIE0_RXP_M0/SATA0_RXP_M0/USB_DRD0_SSRXP>_D43") (pintype "power_in"))
    )
    (net (code "203") (name "Net-(CON0D-H32{slash}<PCIE0_RXP_M1{slash}SATA0_RXP_M1{slash}USB_DRD1_SSRXP>)") (class "Default")
      (node (ref "C439") (pin "2") (pinfunction "2_2") (pintype "passive"))
      (node (ref "CON0") (pin "D25") (pinfunction "H32/<PCIE0_RXP_M1/SATA0_RXP_M1/USB_DRD1_SSRXP>_D25") (pintype "passive"))
    )
    (net (code "204") (name "Net-(CON0D-H33{slash}<PCIE0_RXN_M1{slash}SATA0_RXN_M1{slash}USB_DRD1_SSRXN>)") (class "Default")
      (node (ref "C438") (pin "2") (pinfunction "2_2") (pintype "passive"))
      (node (ref "CON0") (pin "D23") (pinfunction "H33/<PCIE0_RXN_M1/SATA0_RXN_M1/USB_DRD1_SSRXN>_D23") (pintype "passive"))
    )
    (net (code "205") (name "Net-(U1-OE)") (class "Default")
      (node (ref "R9") (pin "2") (pinfunction "2_2") (pintype "passive"))
      (node (ref "U1") (pin "6") (pinfunction "OE_6") (pintype "passive"))
    )
    (net (code "206") (name "Net-(U2-OE)") (class "Default")
      (node (ref "R609") (pin "2") (pinfunction "2_2") (pintype "passive"))
      (node (ref "U2") (pin "6") (pinfunction "OE_6") (pintype "passive"))
    )
    (net (code "207") (name "P32{slash}NPOR_u{slash}PU{slash}1V8") (class "Default")
      (node (ref "CON0") (pin "D2") (pinfunction "P32/<NPOR_u>/1V8_D2") (pintype "passive"))
    )
    (net (code "208") (name "RK806S_PWRON{slash}PU{slash}5V") (class "Default")
      (node (ref "CON0") (pin "D15") (pinfunction "RK806S_PWRON_D15") (pintype "passive"))
    )
    (net (code "209") (name "T32{slash}I2C1_SCL_M0{slash}1V8") (class "Default")
      (node (ref "CON0") (pin "D6") (pinfunction "T32/<I2C1_SCL_M0/SPI2_CLK_M0/GPIO0_B2_z>/1V8_D6") (pintype "passive"))
      (node (ref "R621") (pin "2") (pinfunction "2_2") (pintype "passive"))
      (node (ref "U2") (pin "4") (pinfunction "A2_4") (pintype "passive"))
    )
    (net (code "210") (name "T32{slash}I2C1_SCL_M0{slash}3V3") (class "Default")
      (node (ref "R4") (pin "2") (pinfunction "2_2") (pintype "passive"))
      (node (ref "U2") (pin "1") (pinfunction "B2_1") (pintype "passive"))
    )
    (net (code "211") (name "T33{slash}SDMMC0_DETN_M0{slash}1V8") (class "Default")
      (node (ref "CON0") (pin "D8") (pinfunction "T33/<SPI2_CSN1_M0/SDMMC0_DETN_M0/GPIO0_A7_u>/1V8_D8") (pintype "passive"))
    )
    (net (code "212") (name "U33{slash}UART0_TX_M0{slash}3V3") (class "Default")
      (node (ref "CON0") (pin "B4") (pinfunction "U33/<JTAG_TCK_M1/UART0_TX_M0/GPIO0_D4_u>/3V3_B4") (pintype "power_in"))
    )
    (net (code "213") (name "V32{slash}UART0_RX_M0{slash}3V3") (class "Default")
      (node (ref "CON0") (pin "B6") (pinfunction "V32/<JTAG_TMS_M1/UART0_RX_M0/GPIO0_D5_u>/3V3_B6") (pintype "power_in"))
    )
    (net (code "214") (name "VDD_1V8_MAIN") (class "Default")
      (node (ref "C11") (pin "1") (pinfunction "1_1") (pintype "passive"))
      (node (ref "C9") (pin "1") (pinfunction "1_1") (pintype "passive"))
      (node (ref "R601") (pin "2") (pinfunction "2_2") (pintype "passive"))
      (node (ref "R602") (pin "2") (pinfunction "2_2") (pintype "passive"))
      (node (ref "R609") (pin "1") (pinfunction "1_1") (pintype "passive"))
      (node (ref "R620") (pin "1") (pinfunction "1_1") (pintype "passive"))
      (node (ref "R621") (pin "1") (pinfunction "1_1") (pintype "passive"))
      (node (ref "R622") (pin "1") (pinfunction "1_1") (pintype "passive"))
      (node (ref "R623") (pin "1") (pinfunction "1_1") (pintype "passive"))
      (node (ref "R9") (pin "1") (pinfunction "1_1") (pintype "passive"))
      (node (ref "U1") (pin "3") (pinfunction "VCCA_3") (pintype "passive"))
      (node (ref "U2") (pin "3") (pinfunction "VCCA_3") (pintype "passive"))
    )
    (net (code "215") (name "VDD_3V3_MAIN") (class "Default")
      (node (ref "C10") (pin "1") (pinfunction "1_1") (pintype "passive"))
      (node (ref "C8") (pin "1") (pinfunction "1_1") (pintype "passive"))
      (node (ref "R3") (pin "1") (pinfunction "1_1") (pintype "passive"))
      (node (ref "R4") (pin "1") (pinfunction "1_1") (pintype "passive"))
      (node (ref "R7") (pin "1") (pinfunction "1_1") (pintype "passive"))
      (node (ref "R8") (pin "1") (pinfunction "1_1") (pintype "passive"))
      (node (ref "U1") (pin "7") (pinfunction "VCCB_7") (pintype "passive"))
      (node (ref "U2") (pin "7") (pinfunction "VCCB_7") (pintype "passive"))
    )
    (net (code "216") (name "VDD_3V3_SOM_OUTPUT") (class "Default")
      (node (ref "C12") (pin "1") (pinfunction "1_1") (pintype "passive"))
      (node (ref "C13") (pin "1") (pinfunction "1_1") (pintype "passive"))
      (node (ref "CON0") (pin "D17") (pinfunction "VDD_3V3_SOM_OUT_D17") (pintype "passive"))
    )
    (net (code "217") (name "VDD_5V_SOM") (class "Default")
      (node (ref "C1") (pin "1") (pinfunction "1_1") (pintype "passive"))
      (node (ref "C2") (pin "1") (pinfunction "1_1") (pintype "passive"))
      (node (ref "C3") (pin "1") (pinfunction "1_1") (pintype "passive"))
      (node (ref "CON0") (pin "D1") (pinfunction "VDD_5V_SOM_D1") (pintype "power_in"))
      (node (ref "CON0") (pin "D3") (pinfunction "VDD_5V_SOM_D3") (pintype "power_in"))
      (node (ref "CON0") (pin "D5") (pinfunction "VDD_5V_SOM_D5") (pintype "power_in"))
    )
    (net (code "218") (name "VDD_SD_ADJ") (class "Default")
      (node (ref "CON0") (pin "D19") (pinfunction "VDD_ADJ_SD_D19") (pintype "passive"))
    )
    (net (code "219") (name "W32{slash}UART8_RX_M1{slash}3V3") (class "Default")
      (node (ref "CON0") (pin "B8") (pinfunction "W32/<I3C_SDA_M0/UART8_RX_M1/GPIO0_C2_d>/3V3_B8") (pintype "passive"))
    )
    (net (code "220") (name "Y32{slash}UART1_RX_M0{slash}3V3") (class "Default")
      (node (ref "CON0") (pin "B20") (pinfunction "Y32/<PWM1_CH3_M0/I2C2_SDA_M0/UART1_RX_M0/CPULIT_AVS/GPIO0_C0_d>/3V3_B20") (pintype "power_in"))
    )
    (net (code "221") (name "Y33{slash}UART8_TX_M1{slash}3V3") (class "Default")
      (node (ref "CON0") (pin "B18") (pinfunction "Y33/<I3C_SCL_M0/UART8_TX_M1/GPIO0_C1_d>/3V3_B18") (pintype "passive"))
    )
    (net (code "222") (name "unconnected-(CON0A-NC1-PadA44)") (class "Default")
      (node (ref "CON0") (pin "A44") (pinfunction "NC1_A44") (pintype "passive+no_connect"))
    )
    (net (code "223") (name "unconnected-(CON0A-NC2-PadA46)") (class "Default")
      (node (ref "CON0") (pin "A46") (pinfunction "NC2_A46") (pintype "passive+no_connect"))
    )
    (net (code "224") (name "unconnected-(CON0A-NC3-PadA48)") (class "Default")
      (node (ref "CON0") (pin "A48") (pinfunction "NC3_A48") (pintype "passive+no_connect"))
    )
    (net (code "225") (name "unconnected-(CON0A-NC4-PadA50)") (class "Default")
      (node (ref "CON0") (pin "A50") (pinfunction "NC4_A50") (pintype "passive+no_connect"))
    )
    (net (code "226") (name "unconnected-(CON0A-NC5-PadA52)") (class "Default")
      (node (ref "CON0") (pin "A52") (pinfunction "NC5_A52") (pintype "passive+no_connect"))
    )
    (net (code "227") (name "unconnected-(CON0A-NC6-PadA54)") (class "Default")
      (node (ref "CON0") (pin "A54") (pinfunction "NC6_A54") (pintype "passive+no_connect"))
    )
    (net (code "228") (name "unconnected-(CON0A-NC7-PadA56)") (class "Default")
      (node (ref "CON0") (pin "A56") (pinfunction "NC7_A56") (pintype "passive+no_connect"))
    )
    (net (code "229") (name "unconnected-(CON0A-NC8-PadA58)") (class "Default")
      (node (ref "CON0") (pin "A58") (pinfunction "NC8_A58") (pintype "passive+no_connect"))
    )
    (net (code "230") (name "unconnected-(CON0A-NC9-PadA60)") (class "Default")
      (node (ref "CON0") (pin "A60") (pinfunction "NC9_A60") (pintype "passive+no_connect"))
    )
    (net (code "231") (name "unconnected-(CON0A-NC10-PadA64)") (class "Default")
      (node (ref "CON0") (pin "A64") (pinfunction "NC10_A64") (pintype "passive+no_connect"))
    )
    (net (code "232") (name "unconnected-(CON0A-NC11-PadA66)") (class "Default")
      (node (ref "CON0") (pin "A66") (pinfunction "NC11_A66") (pintype "passive+no_connect"))
    )
    (net (code "233") (name "unconnected-(CON0A-NC12-PadA68)") (class "Default")
      (node (ref "CON0") (pin "A68") (pinfunction "NC12_A68") (pintype "passive+no_connect"))
    )
    (net (code "234") (name "unconnected-(CON0D-RK806S_PWR_CTRL2{slash}1V8-PadD13)") (class "Default")
      (node (ref "CON0") (pin "D13") (pinfunction "RK806S_PWR_CTRL2/1V8_D13") (pintype "passive+no_connect"))
    )
  )
)
